# steering_wheel_V2.net
KiCad netlist of a schematic drawn in EAGLE
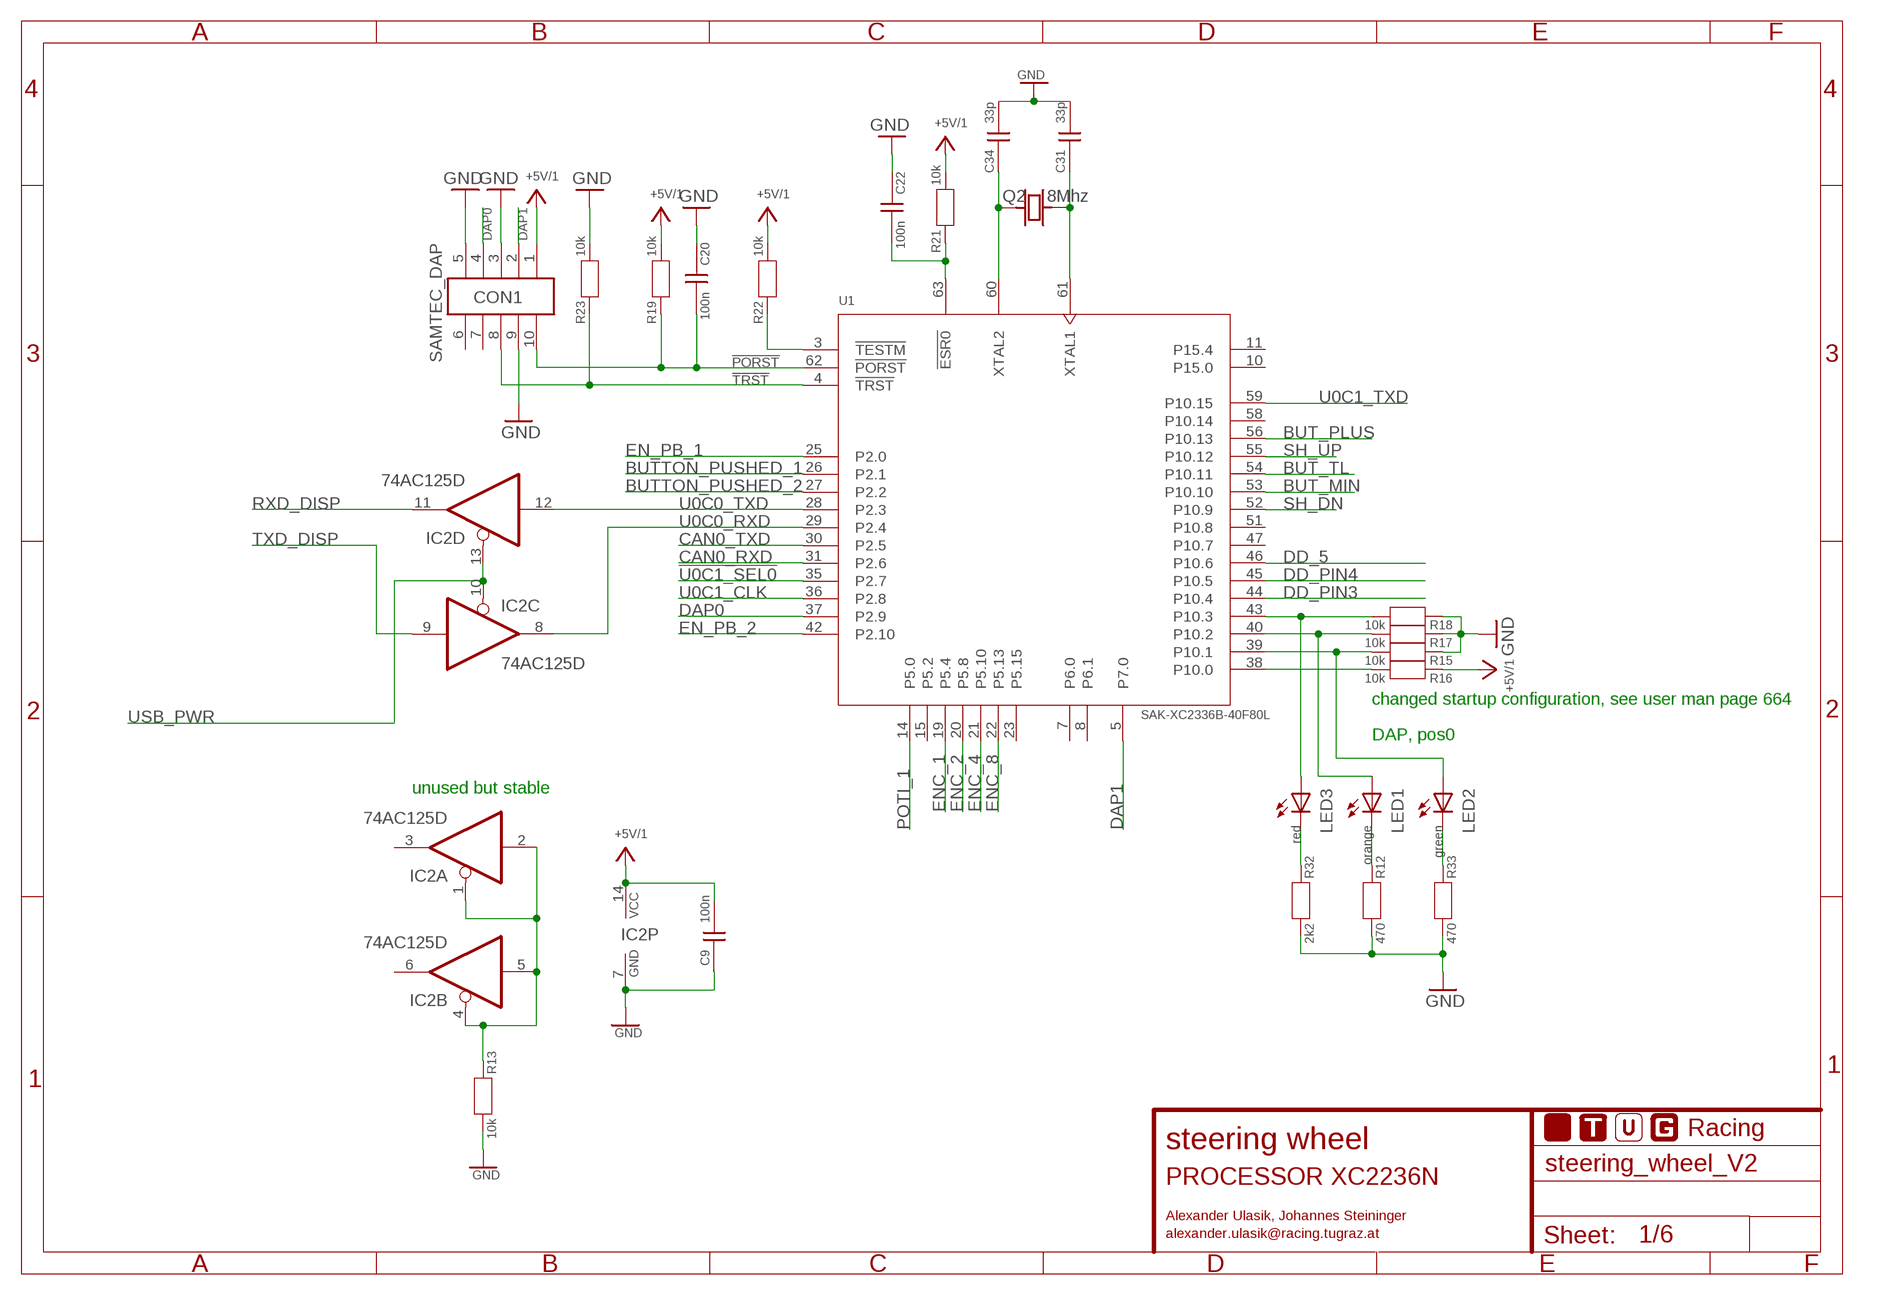
[diagram p0: schematic, sheet 1]
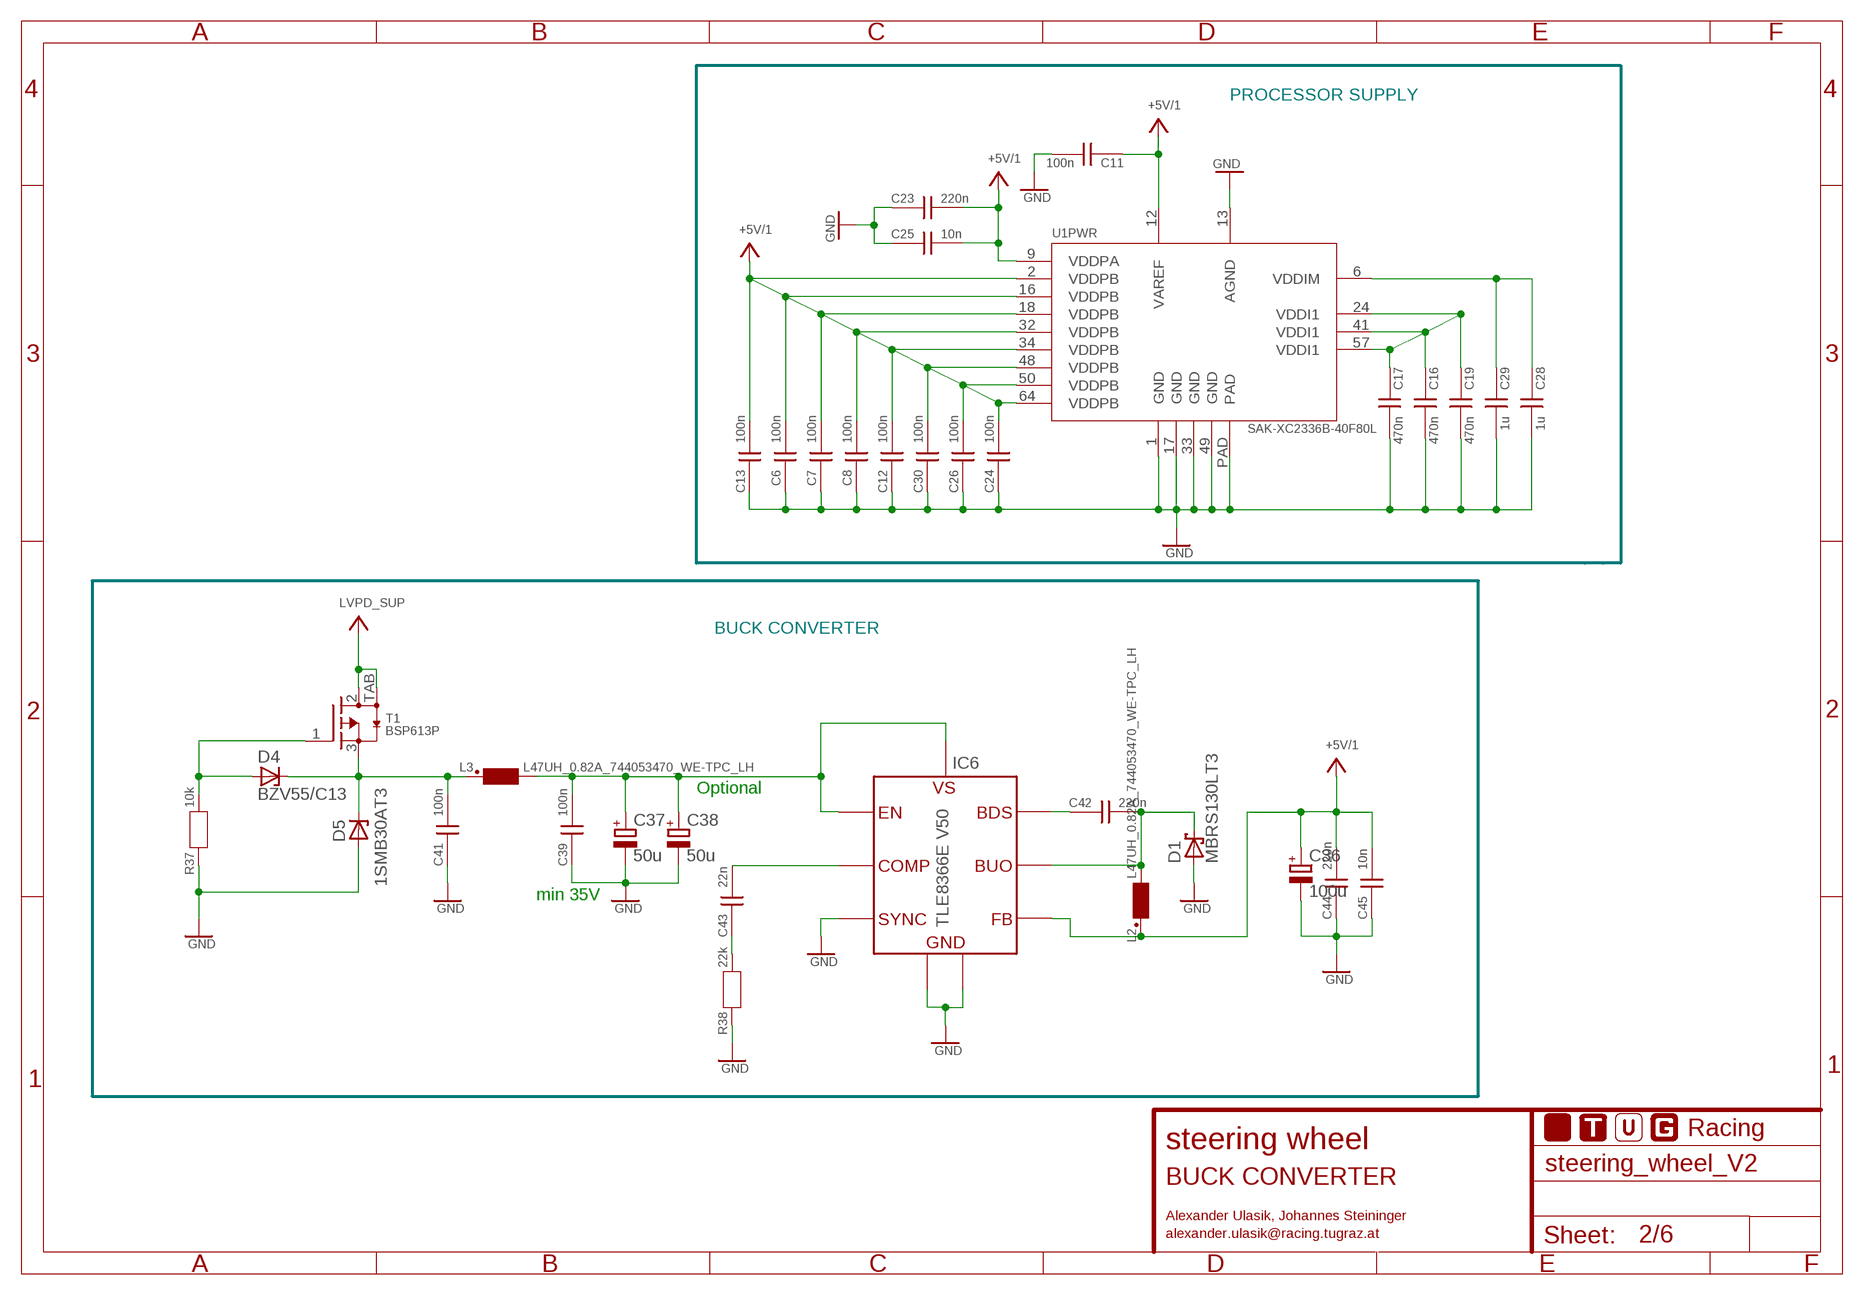
[diagram p1: schematic, sheet 2]
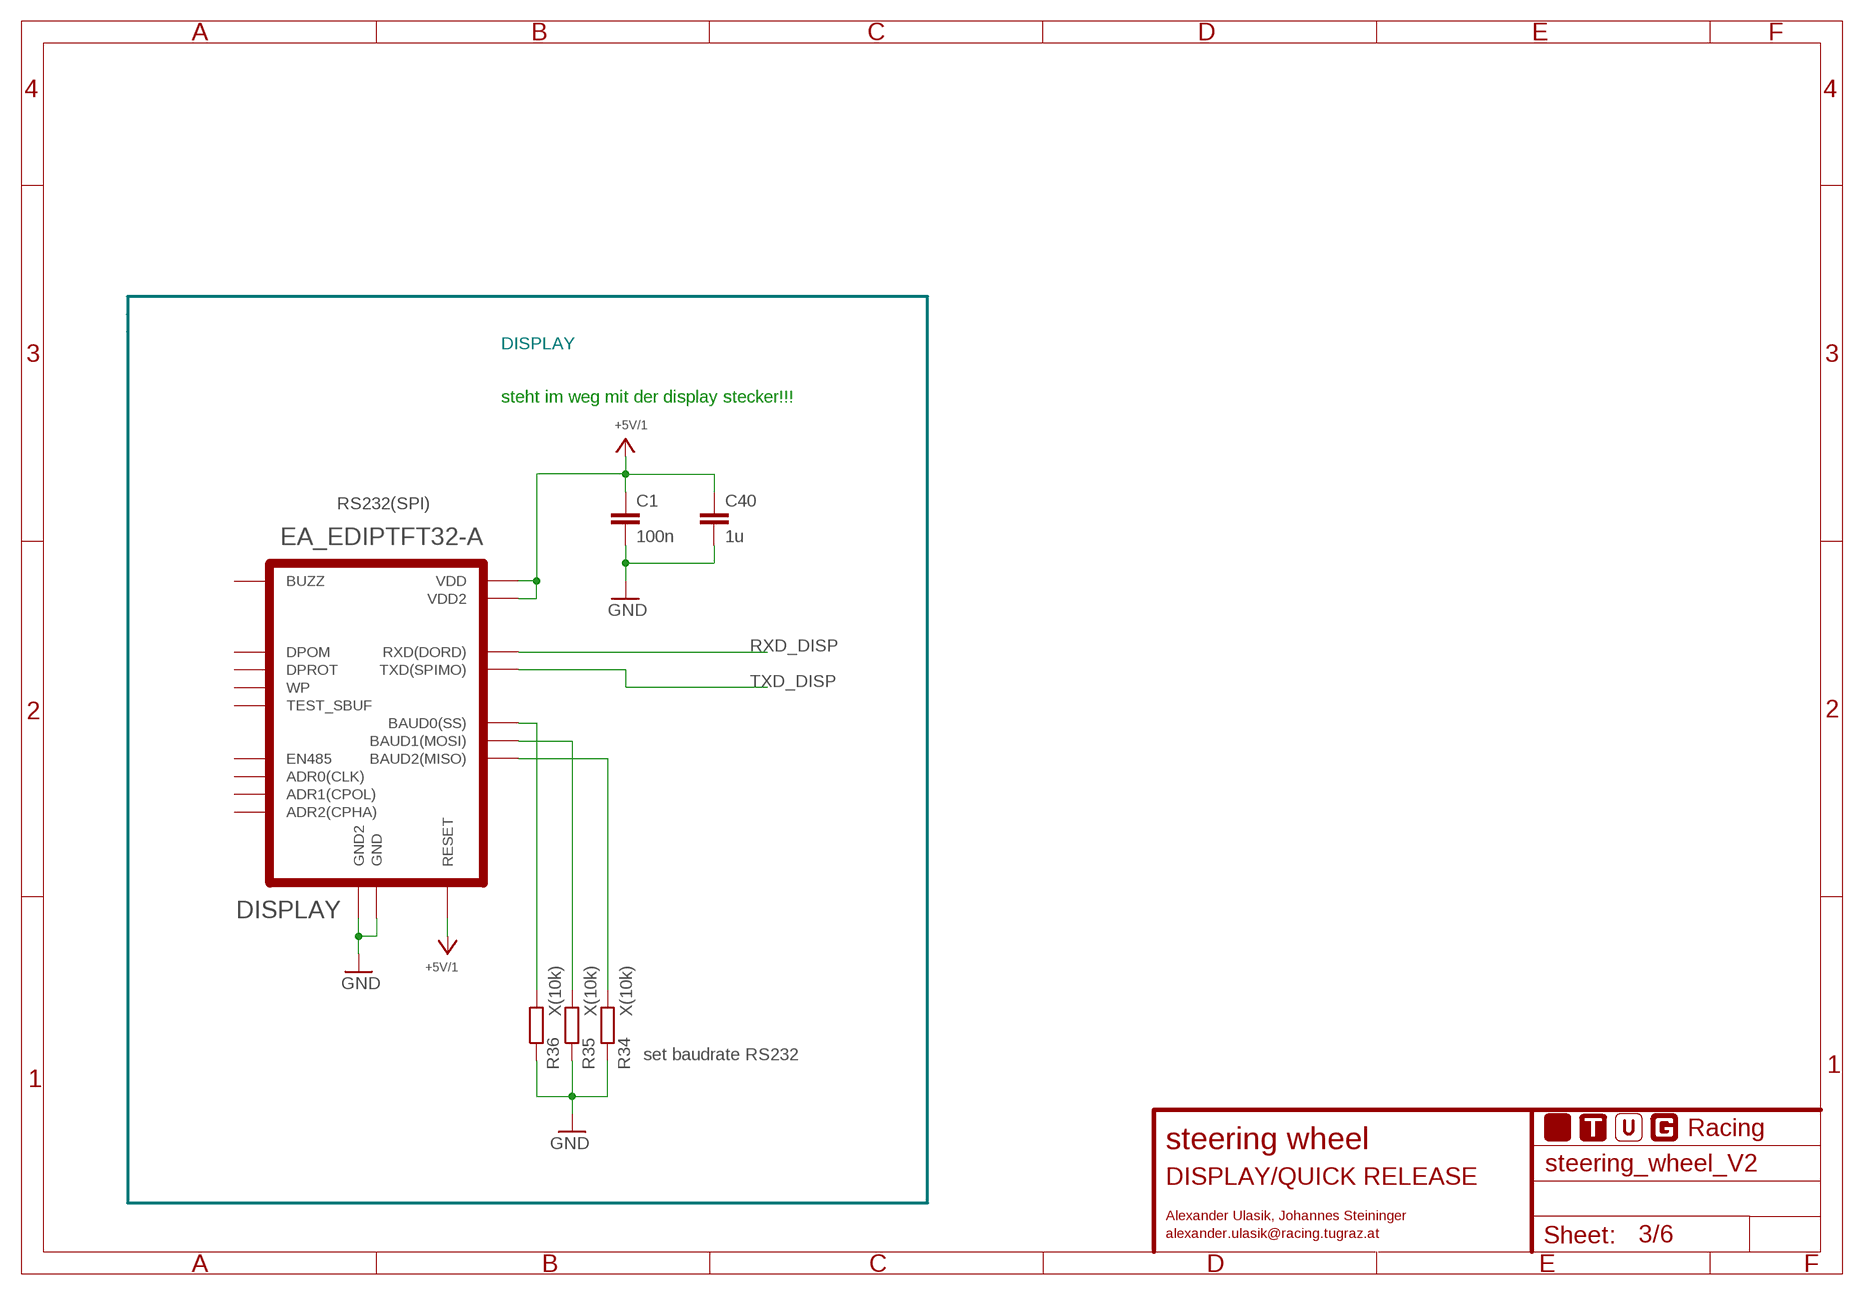
[diagram p2: schematic, sheet 3]
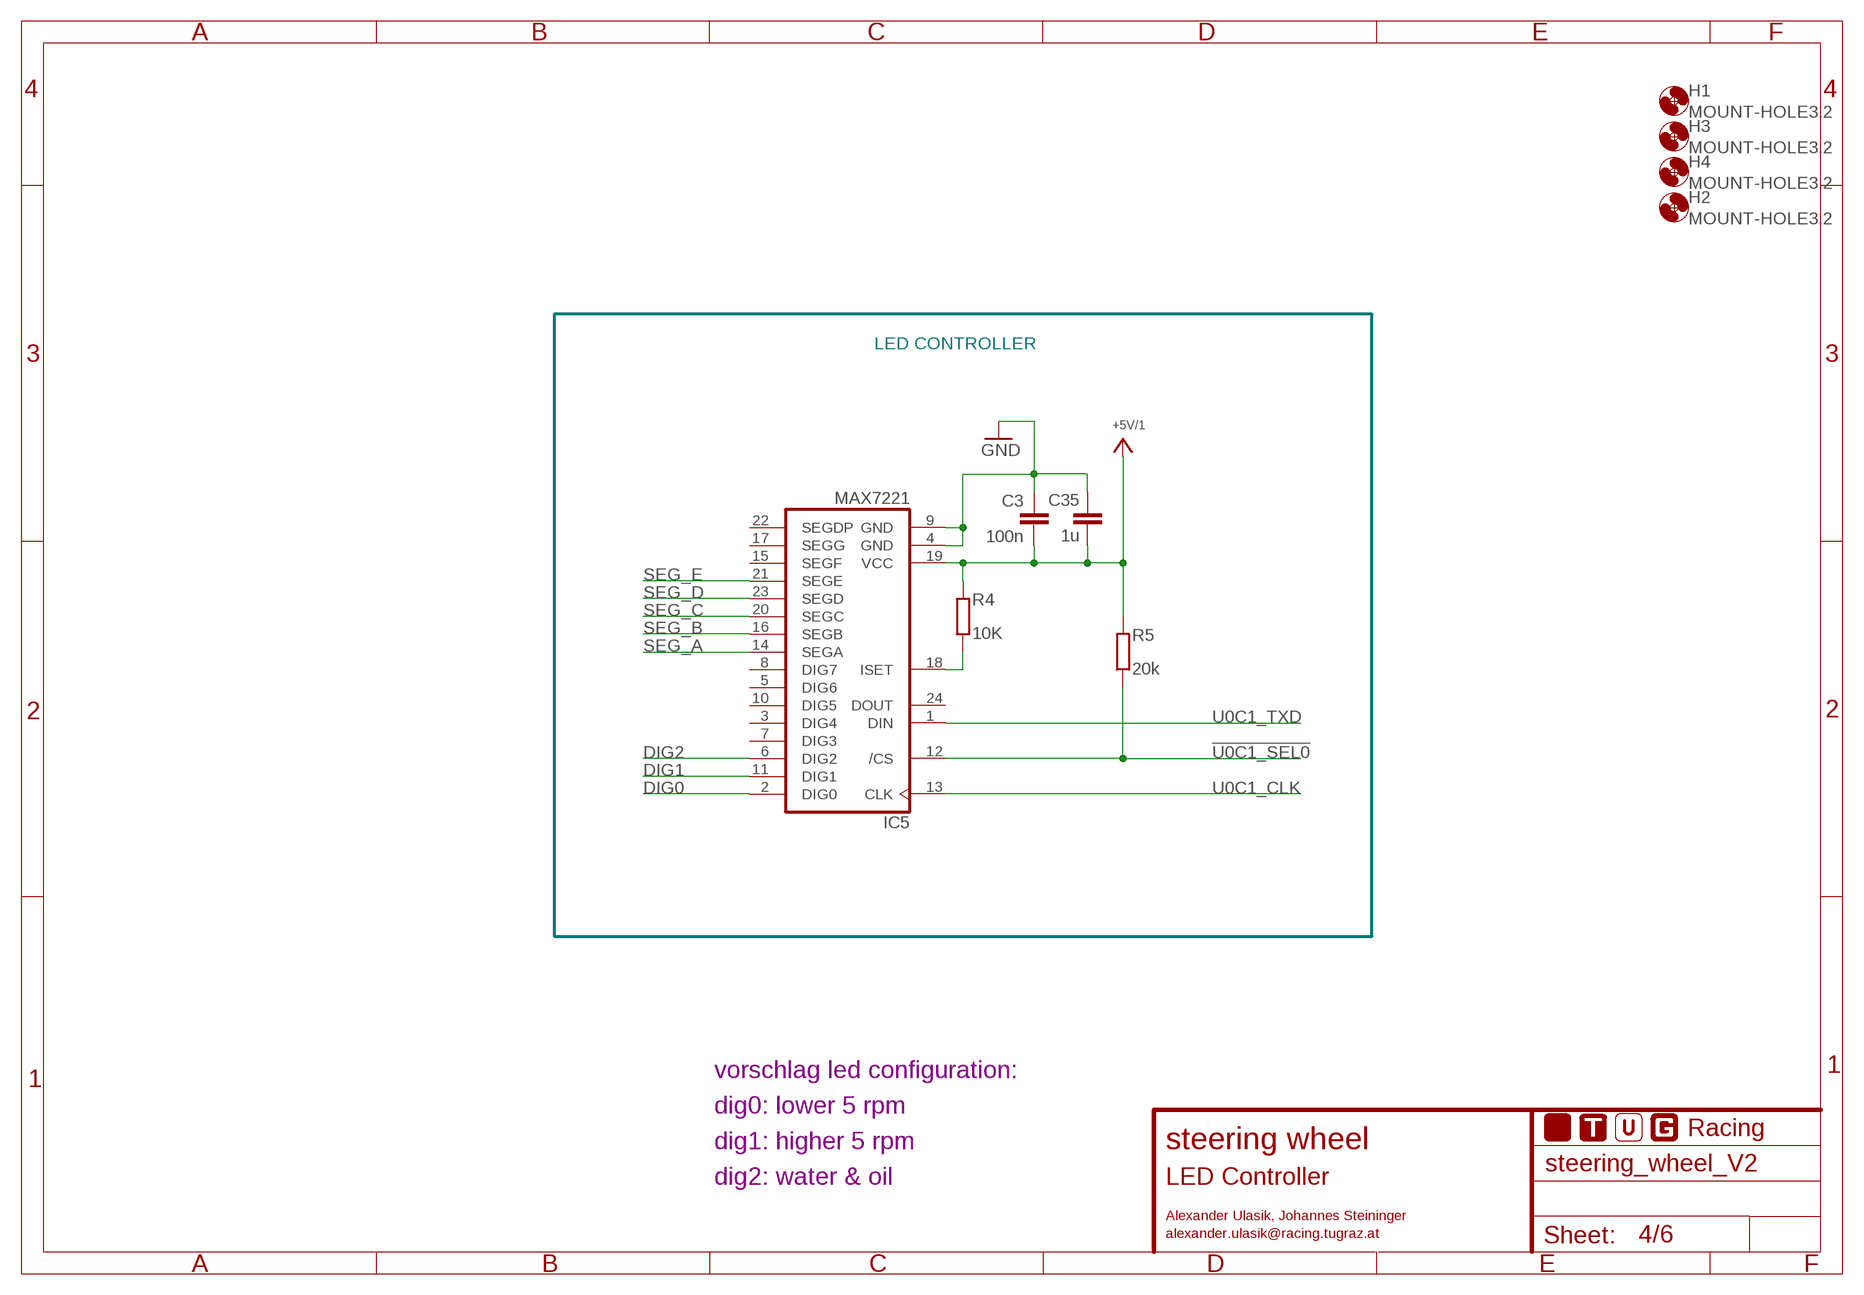
[diagram p3: schematic, sheet 4]
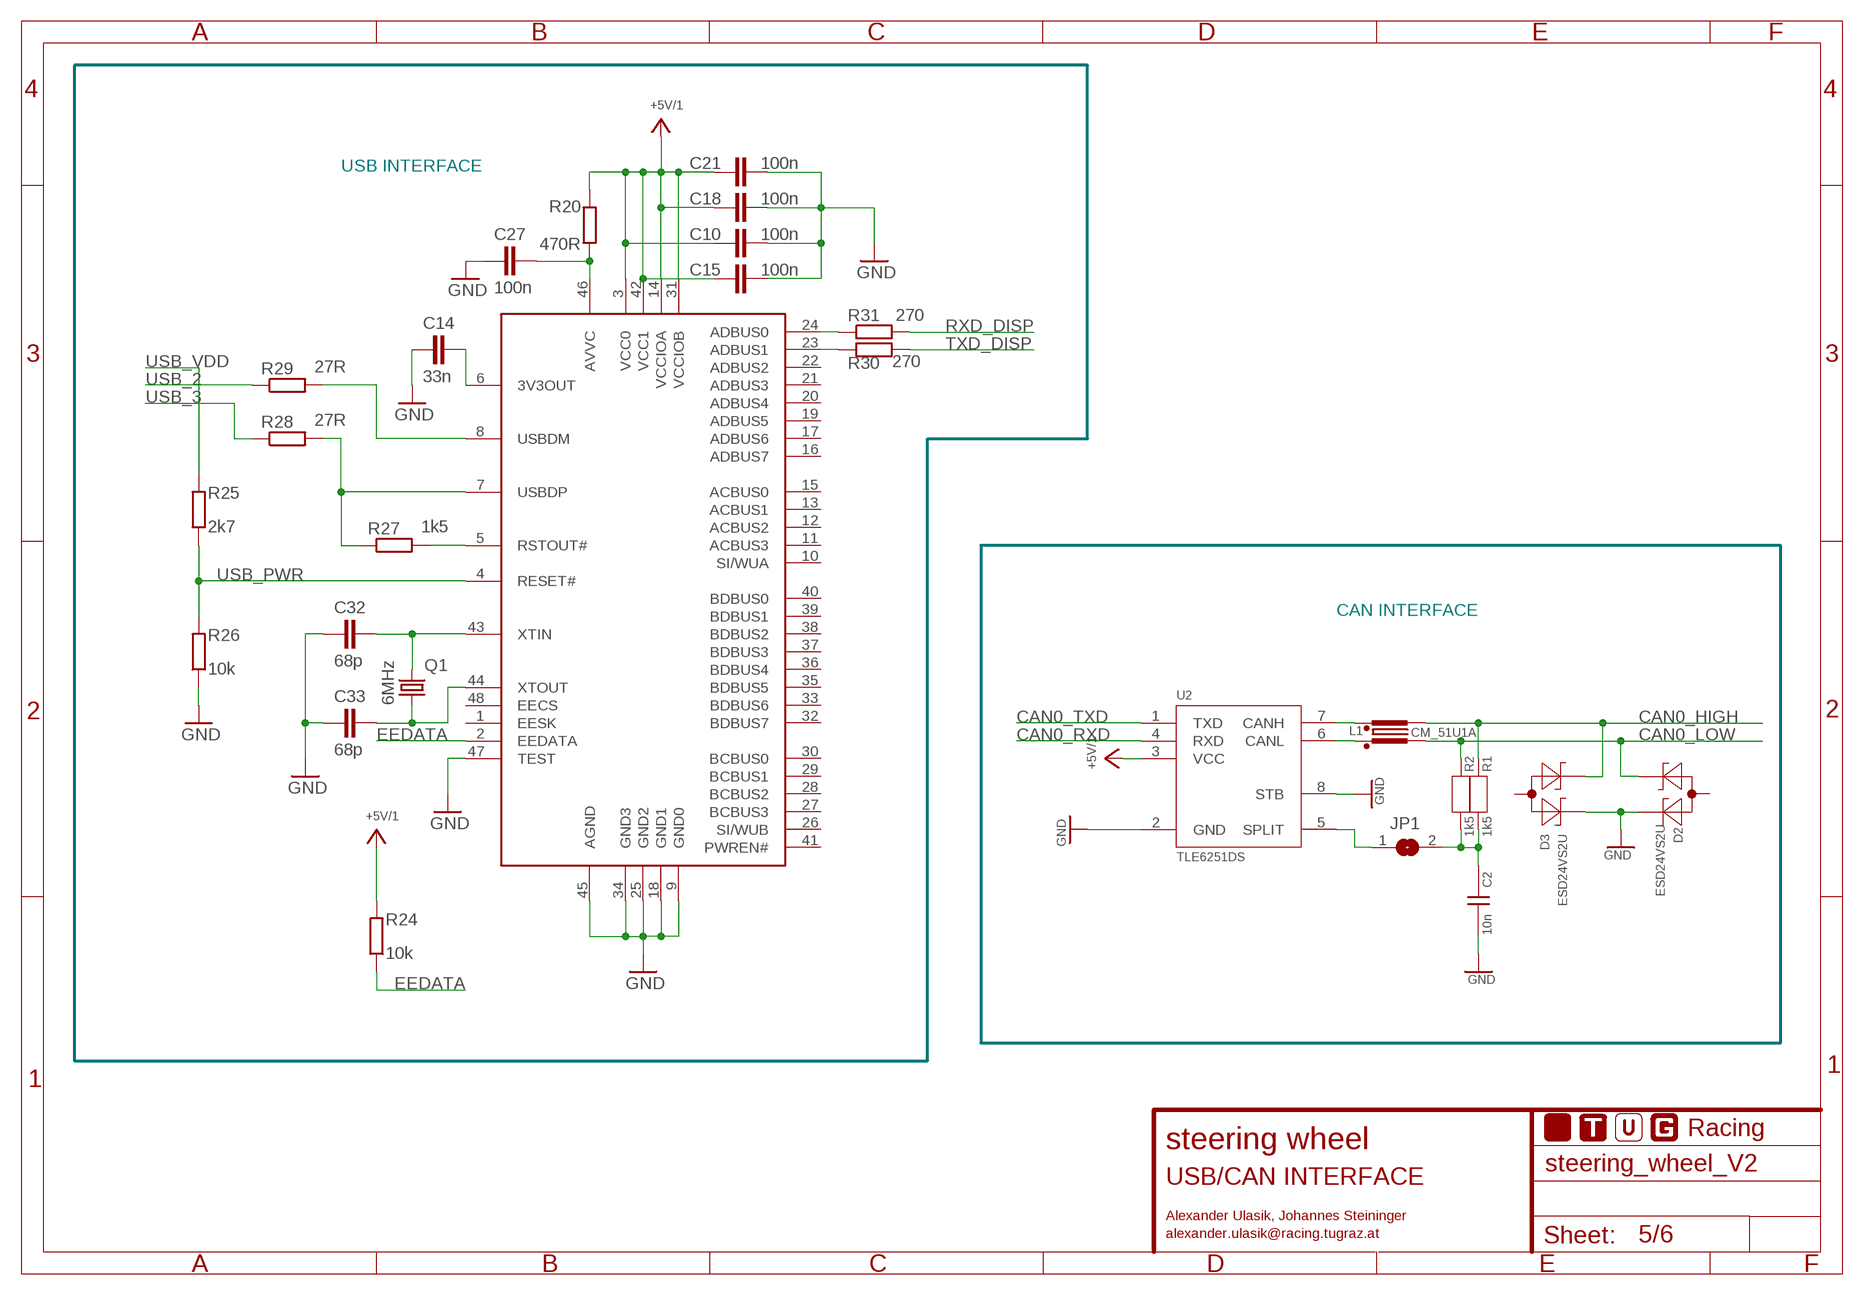
[diagram p4: schematic, sheet 5]
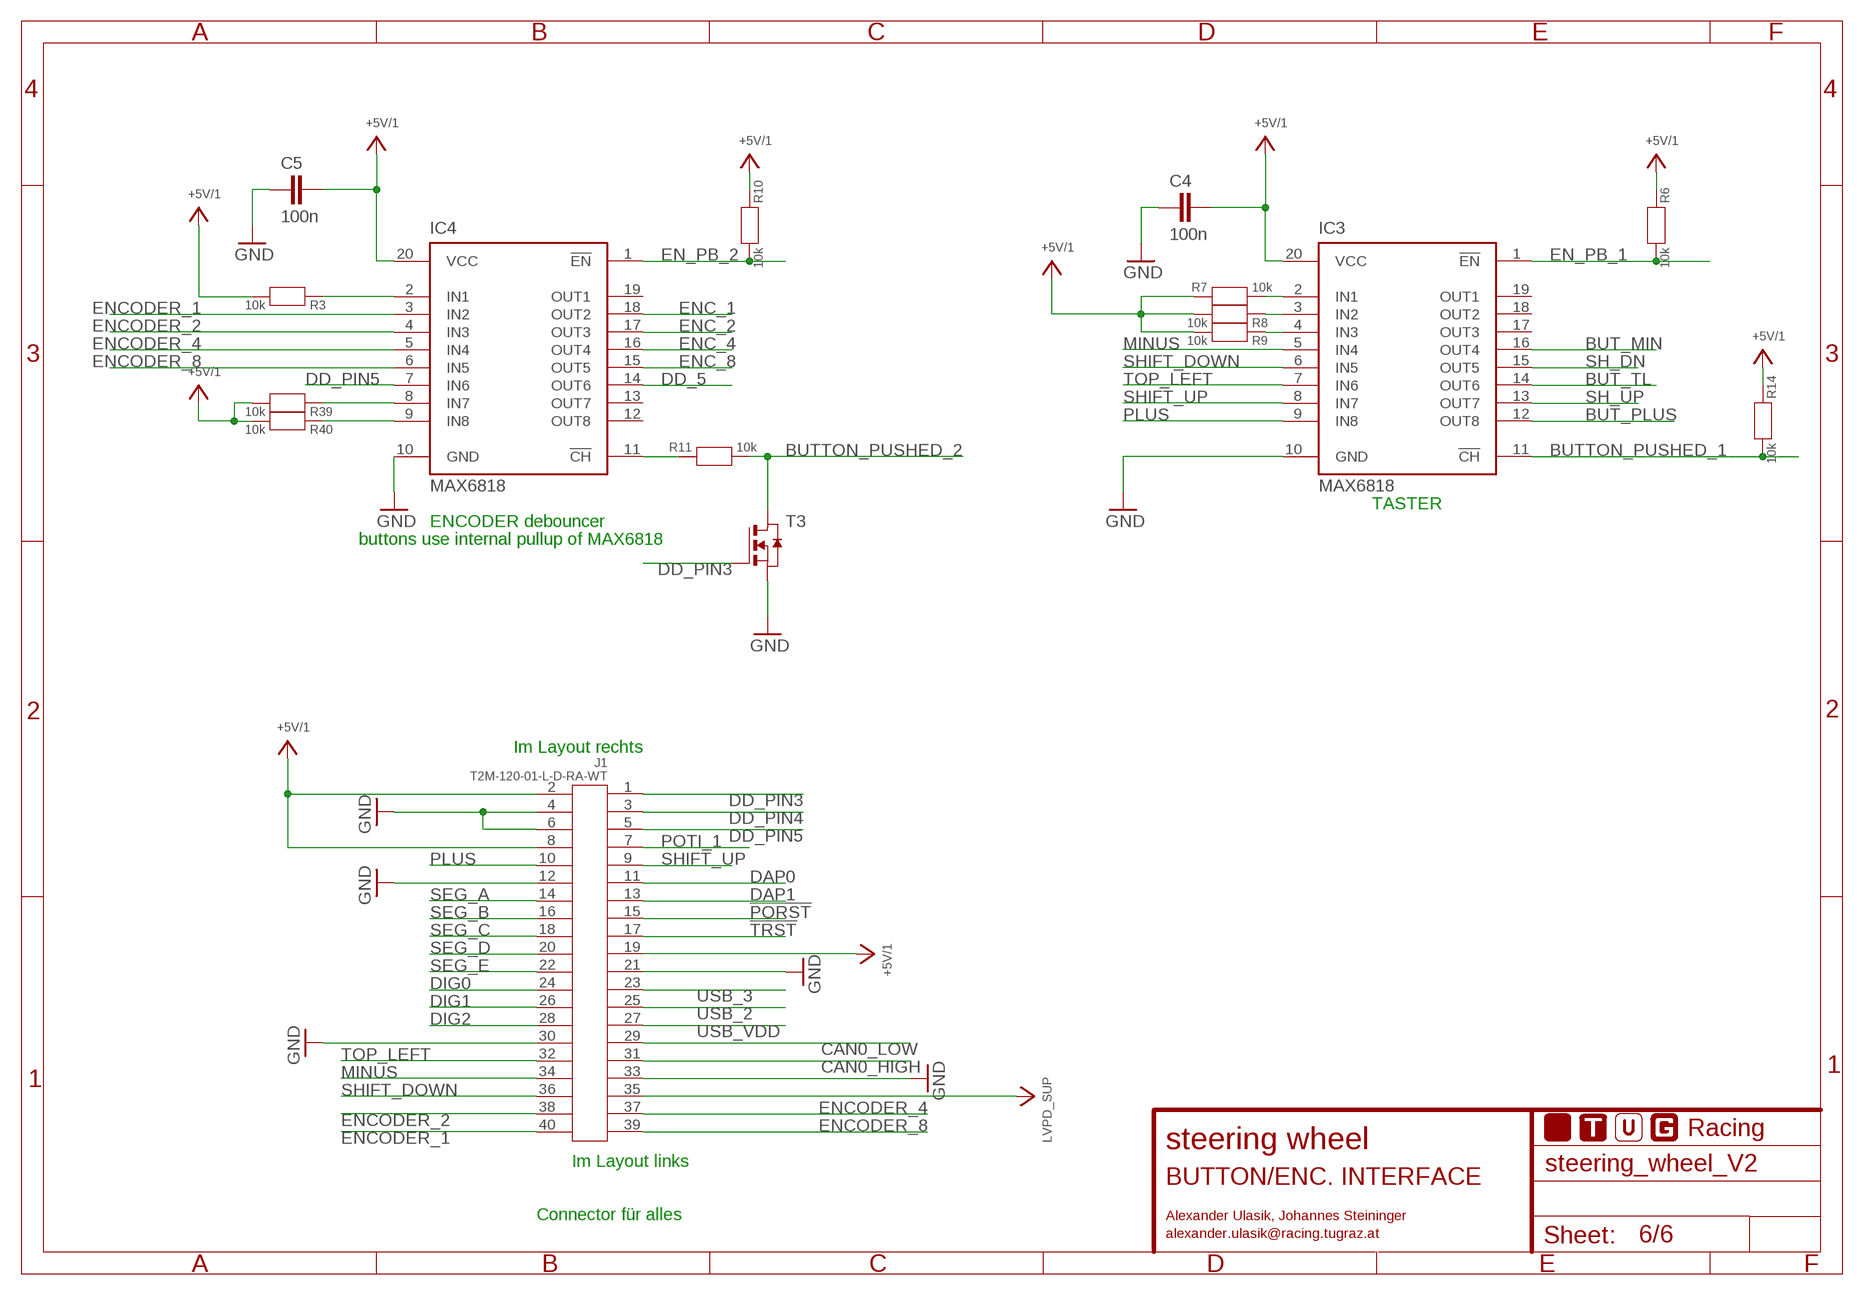
[diagram p5: schematic, sheet 6]

(export (version "E")
  (design (tool "Eeschema 10.0.6"))
  (components
    (comp (ref "C6")
      (value "100n")
      (footprint "eagle-import:2012M_0805")
      (libsource (lib "eagle-import") (part "C_2012M"))
    )
    (comp (ref "C7")
      (value "100n")
      (footprint "eagle-import:2012M_0805")
      (libsource (lib "eagle-import") (part "C_2012M"))
    )
    (comp (ref "C8")
      (value "100n")
      (footprint "eagle-import:2012M_0805")
      (libsource (lib "eagle-import") (part "C_2012M"))
    )
    (comp (ref "C11")
      (value "100n")
      (footprint "eagle-import:2012M_0805")
      (libsource (lib "eagle-import") (part "C_2012M"))
    )
    (comp (ref "C12")
      (value "100n")
      (footprint "eagle-import:2012M_0805")
      (libsource (lib "eagle-import") (part "C_2012M"))
    )
    (comp (ref "C13")
      (value "100n")
      (footprint "eagle-import:2012M_0805")
      (libsource (lib "eagle-import") (part "C_2012M"))
    )
    (comp (ref "C16")
      (value "470n")
      (footprint "eagle-import:2012M_0805")
      (libsource (lib "eagle-import") (part "C_2012M"))
    )
    (comp (ref "C17")
      (value "470n")
      (footprint "eagle-import:2012M_0805")
      (libsource (lib "eagle-import") (part "C_2012M"))
    )
    (comp (ref "C19")
      (value "470n")
      (footprint "eagle-import:2012M_0805")
      (libsource (lib "eagle-import") (part "C_2012M"))
    )
    (comp (ref "C23")
      (value "220n")
      (footprint "eagle-import:2012M_0805")
      (libsource (lib "eagle-import") (part "C_2012M"))
    )
    (comp (ref "C24")
      (value "100n")
      (footprint "eagle-import:2012M_0805")
      (libsource (lib "eagle-import") (part "C_2012M"))
    )
    (comp (ref "C25")
      (value "10n")
      (footprint "eagle-import:2012M_0805")
      (libsource (lib "eagle-import") (part "C_2012M"))
    )
    (comp (ref "C26")
      (value "100n")
      (footprint "eagle-import:2012M_0805")
      (libsource (lib "eagle-import") (part "C_2012M"))
    )
    (comp (ref "C28")
      (value "1u")
      (footprint "eagle-import:2012M_0805")
      (libsource (lib "eagle-import") (part "C_2012M"))
    )
    (comp (ref "C29")
      (value "1u")
      (footprint "eagle-import:2012M_0805")
      (libsource (lib "eagle-import") (part "C_2012M"))
    )
    (comp (ref "C30")
      (value "100n")
      (footprint "eagle-import:2012M_0805")
      (libsource (lib "eagle-import") (part "C_2012M"))
    )
    (comp (ref "C36")
      (value "100u")
      (footprint "eagle-import:E5-10,5")
      (libsource (lib "eagle-import") (part "CPOL-EUE5-10.5"))
    )
    (comp (ref "C37")
      (value "50u")
      (footprint "eagle-import:E5-10,5")
      (libsource (lib "eagle-import") (part "CPOL-EUE5-10.5"))
    )
    (comp (ref "C38")
      (value "50u")
      (footprint "eagle-import:E5-10,5")
      (libsource (lib "eagle-import") (part "CPOL-EUE5-10.5"))
    )
    (comp (ref "C39")
      (value "100n")
      (footprint "eagle-import:2012M_0805")
      (libsource (lib "eagle-import") (part "C_2012M"))
    )
    (comp (ref "C41")
      (value "100n")
      (footprint "eagle-import:2012M_0805")
      (libsource (lib "eagle-import") (part "C_2012M"))
    )
    (comp (ref "C42")
      (value "220n")
      (footprint "eagle-import:2012M_0805")
      (libsource (lib "eagle-import") (part "C_2012M"))
    )
    (comp (ref "C43")
      (value "22n")
      (footprint "eagle-import:2012M_0805")
      (libsource (lib "eagle-import") (part "C_2012M"))
    )
    (comp (ref "C44")
      (value "220n")
      (footprint "eagle-import:2012M_0805")
      (libsource (lib "eagle-import") (part "C_2012M"))
    )
    (comp (ref "C45")
      (value "10n")
      (footprint "eagle-import:2012M_0805")
      (libsource (lib "eagle-import") (part "C_2012M"))
    )
    (comp (ref "D1")
      (value "MBRS130LT3")
      (footprint "eagle-import:SMB")
      (libsource (lib "eagle-import") (part "MBRS130LT3"))
    )
    (comp (ref "D4")
      (value "BZV55/C13")
      (footprint "eagle-import:SOD80C")
      (libsource (lib "eagle-import") (part "diode_ZENER-DIODESOD80C"))
    )
    (comp (ref "D5")
      (value "1SMB30AT3")
      (footprint "eagle-import:SMB")
      (libsource (lib "eagle-import") (part "ZENER-DIODESMB"))
    )
    (comp (ref "FRAME4")
      (value "A4L-LOC-RACING-BRD-TPLACE")
      (footprint "eagle-import:LOGO_RACING_BRD_TPLACE")
      (fields
        (field (name "FRAME_EMAIL") "alexander.ulasik@racing.tugraz.at")
        (field (name "FRAME_SUBTITLE") "BUCK CONVERTER")
        (field (name "FRAME_TITLE") "steering wheel")
        (field (name "FRAME_USER") "Alexander Ulasik, Johannes Steininger")
      )
      (libsource (lib "eagle-import") (part "A4L-LOC-RACING-BRD-TPLACE"))
    )
    (comp (ref "IC6")
      (value "TLE8366E V50")
      (footprint "eagle-import:SOIC08-II")
      (libsource (lib "eagle-import") (part "TLE8366-II"))
    )
    (comp (ref "L2")
      (value "L47UH_0.82A_744053470_WE-TPC_LH")
      (footprint "eagle-import:WE-TPC_LH")
      (libsource (lib "eagle-import") (part "L_WE-TPC_LH47UH_0.82A_744053470"))
    )
    (comp (ref "L3")
      (value "L47UH_0.82A_744053470_WE-TPC_LH")
      (footprint "eagle-import:WE-TPC_LH")
      (libsource (lib "eagle-import") (part "L_WE-TPC_LH47UH_0.82A_744053470"))
    )
    (comp (ref "R37")
      (value "10k")
      (footprint "eagle-import:2012M_0805")
      (libsource (lib "eagle-import") (part "R_2012M"))
    )
    (comp (ref "R38")
      (value "22k")
      (footprint "eagle-import:2012M_0805")
      (libsource (lib "eagle-import") (part "R_2012M"))
    )
    (comp (ref "T1")
      (value "BSP613P")
      (footprint "eagle-import:SOT223-3")
      (libsource (lib "eagle-import") (part "BSP613P"))
    )
    (comp (ref "U1")
      (value "SAK-XC2336B-40F80L")
      (footprint "eagle-import:PG-LQFP-64-6")
      (libsource (lib "eagle-import") (part "SAK-XC2336B-40F80L"))
    )
    (comp (ref "C9")
      (value "100n")
      (footprint "eagle-import:1608M_0603")
      (libsource (lib "eagle-import") (part "C_1608M"))
    )
    (comp (ref "C20")
      (value "100n")
      (footprint "eagle-import:2012M_0805")
      (libsource (lib "eagle-import") (part "C_2012M"))
    )
    (comp (ref "C22")
      (value "100n")
      (footprint "eagle-import:2012M_0805")
      (libsource (lib "eagle-import") (part "C_2012M"))
    )
    (comp (ref "C31")
      (value "33p")
      (footprint "eagle-import:1608M_0603")
      (libsource (lib "eagle-import") (part "C_1608M"))
    )
    (comp (ref "C34")
      (value "33p")
      (footprint "eagle-import:1608M_0603")
      (libsource (lib "eagle-import") (part "C_1608M"))
    )
    (comp (ref "CON1")
      (value "SAMTEC_DAP")
      (footprint "eagle-import:FTSH-105-01-XXX-DV-K")
      (libsource (lib "eagle-import") (part "SAMTEC_DAP"))
    )
    (comp (ref "FRAME1")
      (value "A4L-LOC-RACING-NOLOGO")
      (footprint "eagle-import:NOLOGO")
      (fields
        (field (name "FRAME_EMAIL") "alexander.ulasik@racing.tugraz.at")
        (field (name "FRAME_SUBTITLE") "PROCESSOR XC2236N ")
        (field (name "FRAME_TITLE") "steering wheel")
        (field (name "FRAME_USER") "Alexander Ulasik, Johannes Steininger")
      )
      (libsource (lib "eagle-import") (part "A4L-LOC-RACING-NOLOGO"))
    )
    (comp (ref "IC2")
      (value "74AC125D")
      (footprint "eagle-import:SO14")
      (libsource (lib "eagle-import") (part "74125DAC"))
    )
    (comp (ref "LED1")
      (value "LEDCHIPLED_0805")
      (footprint "eagle-import:CHIPLED_0805")
      (fields (field (name "ASMT-RJ45-AQ502") "orange"))
      (libsource (lib "eagle-import") (part "LEDCHIPLED_0805"))
    )
    (comp (ref "LED2")
      (value "LEDCHIPLED_0805")
      (footprint "eagle-import:CHIPLED_0805")
      (fields (field (name "ASMT-RF45-AQ502") "green"))
      (libsource (lib "eagle-import") (part "LEDCHIPLED_0805"))
    )
    (comp (ref "LED3")
      (value "LEDCHIPLED_0805")
      (footprint "eagle-import:CHIPLED_0805")
      (fields (field (name "ASMT-RR45-AQ502") "red"))
      (libsource (lib "eagle-import") (part "LEDCHIPLED_0805"))
    )
    (comp (ref "Q2")
      (value "8Mhz")
      (footprint "eagle-import:ABMM2")
      (libsource (lib "eagle-import") (part "ABMM2"))
    )
    (comp (ref "R12")
      (value "470")
      (footprint "eagle-import:2012M_0805")
      (libsource (lib "eagle-import") (part "R_2012M"))
    )
    (comp (ref "R13")
      (value "10k")
      (footprint "eagle-import:2012M_0805")
      (libsource (lib "eagle-import") (part "R_2012M"))
    )
    (comp (ref "R15")
      (value "10k")
      (footprint "eagle-import:2012M_0805")
      (libsource (lib "eagle-import") (part "R_2012M"))
    )
    (comp (ref "R16")
      (value "10k")
      (footprint "eagle-import:2012M_0805")
      (libsource (lib "eagle-import") (part "R_2012M"))
    )
    (comp (ref "R17")
      (value "10k")
      (footprint "eagle-import:2012M_0805")
      (libsource (lib "eagle-import") (part "R_2012M"))
    )
    (comp (ref "R18")
      (value "10k")
      (footprint "eagle-import:2012M_0805")
      (libsource (lib "eagle-import") (part "R_2012M"))
    )
    (comp (ref "R19")
      (value "10k")
      (footprint "eagle-import:2012M_0805")
      (libsource (lib "eagle-import") (part "R_2012M"))
    )
    (comp (ref "R21")
      (value "10k")
      (footprint "eagle-import:2012M_0805")
      (libsource (lib "eagle-import") (part "R_2012M"))
    )
    (comp (ref "R22")
      (value "10k")
      (footprint "eagle-import:2012M_0805")
      (libsource (lib "eagle-import") (part "R_2012M"))
    )
    (comp (ref "R23")
      (value "10k")
      (footprint "eagle-import:2012M_0805")
      (libsource (lib "eagle-import") (part "R_2012M"))
    )
    (comp (ref "R32")
      (value "2k2")
      (footprint "eagle-import:2012M_0805")
      (libsource (lib "eagle-import") (part "R_2012M"))
    )
    (comp (ref "R33")
      (value "470")
      (footprint "eagle-import:2012M_0805")
      (libsource (lib "eagle-import") (part "R_2012M"))
    )
    (comp (ref "C3")
      (value "100n")
      (footprint "eagle-import:C0805")
      (libsource (lib "eagle-import") (part "C-EUC0805"))
    )
    (comp (ref "C35")
      (value "1u")
      (footprint "eagle-import:C0805")
      (libsource (lib "eagle-import") (part "C-EUC0805"))
    )
    (comp (ref "FRAME5")
      (value "A4L-LOC-RACING-NOLOGO")
      (footprint "eagle-import:NOLOGO")
      (fields
        (field (name "FRAME_EMAIL") "alexander.ulasik@racing.tugraz.at")
        (field (name "FRAME_SUBTITLE") "LED Controller")
        (field (name "FRAME_TITLE") "steering wheel")
        (field (name "FRAME_USER") "Alexander Ulasik, Johannes Steininger")
      )
      (libsource (lib "eagle-import") (part "A4L-LOC-RACING-NOLOGO"))
    )
    (comp (ref "H1")
      (value "MOUNT-HOLE3.2")
      (footprint "eagle-import:3,2")
      (libsource (lib "eagle-import") (part "MOUNT-HOLE3.2"))
    )
    (comp (ref "H2")
      (value "MOUNT-HOLE3.2")
      (footprint "eagle-import:3,2")
      (libsource (lib "eagle-import") (part "MOUNT-HOLE3.2"))
    )
    (comp (ref "H3")
      (value "MOUNT-HOLE3.2")
      (footprint "eagle-import:3,2")
      (libsource (lib "eagle-import") (part "MOUNT-HOLE3.2"))
    )
    (comp (ref "H4")
      (value "MOUNT-HOLE3.2")
      (footprint "eagle-import:3,2")
      (libsource (lib "eagle-import") (part "MOUNT-HOLE3.2"))
    )
    (comp (ref "IC5")
      (value "MAX7221")
      (footprint "eagle-import:SO_W24")
      (libsource (lib "eagle-import") (part "MAX7221"))
    )
    (comp (ref "R4")
      (value "10K")
      (footprint "eagle-import:M0805")
      (libsource (lib "eagle-import") (part "R-EU_M0805"))
    )
    (comp (ref "R5")
      (value "20k")
      (footprint "eagle-import:M0805")
      (libsource (lib "eagle-import") (part "R-EU_M0805"))
    )
    (comp (ref "C4")
      (value "100n")
      (footprint "eagle-import:C0805")
      (libsource (lib "eagle-import") (part "C-EUC0805"))
    )
    (comp (ref "C5")
      (value "100n")
      (footprint "eagle-import:C0805")
      (libsource (lib "eagle-import") (part "C-EUC0805"))
    )
    (comp (ref "FRAME2")
      (value "A4L-LOC-RACING-NOLOGO")
      (footprint "eagle-import:NOLOGO")
      (fields
        (field (name "FRAME_EMAIL") "alexander.ulasik@racing.tugraz.at")
        (field (name "FRAME_SUBTITLE") "BUTTON/ENC. INTERFACE")
        (field (name "FRAME_TITLE") "steering wheel")
        (field (name "FRAME_USER") "Alexander Ulasik, Johannes Steininger")
      )
      (libsource (lib "eagle-import") (part "A4L-LOC-RACING-NOLOGO"))
    )
    (comp (ref "IC3")
      (value "MAX6818")
      (footprint "eagle-import:SSOP20")
      (libsource (lib "eagle-import") (part "MAX6818"))
    )
    (comp (ref "IC4")
      (value "MAX6818")
      (footprint "eagle-import:SSOP20")
      (libsource (lib "eagle-import") (part "MAX6818"))
    )
    (comp (ref "J1")
      (value "T2M-120-01-L-D-RA-WT")
      (footprint "eagle-import:T2M-120-01-L-D-RA-WT")
      (libsource (lib "eagle-import") (part "T2M-120-01-L-D-RA-WT"))
    )
    (comp (ref "R3")
      (value "10k")
      (footprint "eagle-import:2012M_0805")
      (libsource (lib "eagle-import") (part "R_2012M"))
    )
    (comp (ref "R6")
      (value "10k")
      (footprint "eagle-import:2012M_0805")
      (libsource (lib "eagle-import") (part "R_2012M"))
    )
    (comp (ref "R7")
      (value "10k")
      (footprint "eagle-import:2012M_0805")
      (libsource (lib "eagle-import") (part "R_2012M"))
    )
    (comp (ref "R8")
      (value "10k")
      (footprint "eagle-import:2012M_0805")
      (libsource (lib "eagle-import") (part "R_2012M"))
    )
    (comp (ref "R9")
      (value "10k")
      (footprint "eagle-import:2012M_0805")
      (libsource (lib "eagle-import") (part "R_2012M"))
    )
    (comp (ref "R10")
      (value "10k")
      (footprint "eagle-import:2012M_0805")
      (libsource (lib "eagle-import") (part "R_2012M"))
    )
    (comp (ref "R11")
      (value "10k")
      (footprint "eagle-import:2012M_0805")
      (libsource (lib "eagle-import") (part "R_2012M"))
    )
    (comp (ref "R14")
      (value "10k")
      (footprint "eagle-import:2012M_0805")
      (libsource (lib "eagle-import") (part "R_2012M"))
    )
    (comp (ref "R39")
      (value "10k")
      (footprint "eagle-import:2012M_0805")
      (libsource (lib "eagle-import") (part "R_2012M"))
    )
    (comp (ref "R40")
      (value "10k")
      (footprint "eagle-import:2012M_0805")
      (libsource (lib "eagle-import") (part "R_2012M"))
    )
    (comp (ref "T3")
      (value "NMOSSOT23")
      (footprint "eagle-import:SOT-23")
      (libsource (lib "eagle-import") (part "NMOSSOT23"))
    )
    (comp (ref "C2")
      (value "10n")
      (footprint "eagle-import:2012M_0805")
      (libsource (lib "eagle-import") (part "C_2012M"))
    )
    (comp (ref "C10")
      (value "100n")
      (footprint "eagle-import:C0805")
      (libsource (lib "eagle-import") (part "C-EUC0805"))
    )
    (comp (ref "C14")
      (value "33n")
      (footprint "eagle-import:C0805")
      (libsource (lib "eagle-import") (part "C-EUC0805"))
    )
    (comp (ref "C15")
      (value "100n")
      (footprint "eagle-import:C0805")
      (libsource (lib "eagle-import") (part "C-EUC0805"))
    )
    (comp (ref "C18")
      (value "100n")
      (footprint "eagle-import:C0805")
      (libsource (lib "eagle-import") (part "C-EUC0805"))
    )
    (comp (ref "C21")
      (value "100n")
      (footprint "eagle-import:C0805")
      (libsource (lib "eagle-import") (part "C-EUC0805"))
    )
    (comp (ref "C27")
      (value "100n")
      (footprint "eagle-import:C0805")
      (libsource (lib "eagle-import") (part "C-EUC0805"))
    )
    (comp (ref "C32")
      (value "68p")
      (footprint "eagle-import:C0805")
      (libsource (lib "eagle-import") (part "C-EUC0805"))
    )
    (comp (ref "C33")
      (value "68p")
      (footprint "eagle-import:C0805")
      (libsource (lib "eagle-import") (part "C-EUC0805"))
    )
    (comp (ref "D2")
      (value "ESD24VS2U")
      (footprint "eagle-import:SOT23-3")
      (libsource (lib "eagle-import") (part "ESD24VS2U"))
    )
    (comp (ref "D3")
      (value "ESD24VS2U")
      (footprint "eagle-import:SOT23-3")
      (libsource (lib "eagle-import") (part "ESD24VS2U"))
    )
    (comp (ref "FRAME6")
      (value "A4L-LOC-RACING-BRD-TPLACE")
      (footprint "eagle-import:LOGO_RACING_BRD_TPLACE")
      (fields
        (field (name "FRAME_EMAIL") "alexander.ulasik@racing.tugraz.at")
        (field (name "FRAME_SUBTITLE") "USB/CAN INTERFACE")
        (field (name "FRAME_TITLE") "steering wheel")
        (field (name "FRAME_USER") "Alexander Ulasik, Johannes Steininger")
      )
      (libsource (lib "eagle-import") (part "A4L-LOC-RACING-BRD-TPLACE"))
    )
    (comp (ref "IC1")
      (value "FT2232")
      (footprint "eagle-import:LQFP48")
      (libsource (lib "eagle-import") (part "FT2232L"))
    )
    (comp (ref "JP1") (value "SJ") (footprint "eagle-import:SJ") (libsource (lib "eagle-import") (part "SJ")))
    (comp (ref "L1")
      (value "CM_51U1A")
      (footprint "eagle-import:WE-SL2")
      (libsource (lib "eagle-import") (part "CM_51U1A"))
    )
    (comp (ref "Q1")
      (value "6MHz")
      (footprint "eagle-import:HC49U70")
      (libsource (lib "eagle-import") (part "CRYSTALHC49U70"))
    )
    (comp (ref "R1")
      (value "1k5")
      (footprint "eagle-import:2012M_0805")
      (libsource (lib "eagle-import") (part "R_2012M"))
    )
    (comp (ref "R2")
      (value "1k5")
      (footprint "eagle-import:2012M_0805")
      (libsource (lib "eagle-import") (part "R_2012M"))
    )
    (comp (ref "R20")
      (value "470R")
      (footprint "eagle-import:R0805")
      (libsource (lib "eagle-import") (part "R-EU_R0805"))
    )
    (comp (ref "R24")
      (value "10k")
      (footprint "eagle-import:R0805")
      (libsource (lib "eagle-import") (part "R-EU_R0805"))
    )
    (comp (ref "R25")
      (value "2k7")
      (footprint "eagle-import:R0805")
      (libsource (lib "eagle-import") (part "R-EU_R0805"))
    )
    (comp (ref "R26")
      (value "10k")
      (footprint "eagle-import:R0805")
      (libsource (lib "eagle-import") (part "R-EU_R0805"))
    )
    (comp (ref "R27")
      (value "1k5")
      (footprint "eagle-import:R0805")
      (libsource (lib "eagle-import") (part "R-EU_R0805"))
    )
    (comp (ref "R28")
      (value "27R")
      (footprint "eagle-import:R0805")
      (libsource (lib "eagle-import") (part "R-EU_R0805"))
    )
    (comp (ref "R29")
      (value "27R")
      (footprint "eagle-import:R0805")
      (libsource (lib "eagle-import") (part "R-EU_R0805"))
    )
    (comp (ref "R30")
      (value "270")
      (footprint "eagle-import:R0805")
      (libsource (lib "eagle-import") (part "R-EU_R0805"))
    )
    (comp (ref "R31")
      (value "270")
      (footprint "eagle-import:R0805")
      (libsource (lib "eagle-import") (part "R-EU_R0805"))
    )
    (comp (ref "U2")
      (value "TLE6251DS")
      (footprint "eagle-import:SO8")
      (libsource (lib "eagle-import") (part "TLE6251DS"))
    )
    (comp (ref "C1")
      (value "100n")
      (footprint "eagle-import:C0805")
      (libsource (lib "eagle-import") (part "C-EUC0805"))
    )
    (comp (ref "C40")
      (value "1u")
      (footprint "eagle-import:C0805")
      (libsource (lib "eagle-import") (part "C-EUC0805"))
    )
    (comp (ref "DISPLAY")
      (value "EA_EDIPTFT32-A")
      (footprint "eagle-import:EDIPTFT32-A")
      (libsource (lib "eagle-import") (part "EA_EDIPTFT32-A-SR232"))
    )
    (comp (ref "FRAME3")
      (value "A4L-LOC-RACING-NOLOGO")
      (footprint "eagle-import:NOLOGO")
      (fields
        (field (name "FRAME_EMAIL") "alexander.ulasik@racing.tugraz.at")
        (field (name "FRAME_SUBTITLE") "DISPLAY/QUICK RELEASE")
        (field (name "FRAME_TITLE") "steering wheel")
        (field (name "FRAME_USER") "Alexander Ulasik, Johannes Steininger")
      )
      (libsource (lib "eagle-import") (part "A4L-LOC-RACING-NOLOGO"))
    )
    (comp (ref "R34")
      (value "X(10k)")
      (footprint "eagle-import:R0805")
      (libsource (lib "eagle-import") (part "R-EU_R0805"))
    )
    (comp (ref "R35")
      (value "X(10k)")
      (footprint "eagle-import:R0805")
      (libsource (lib "eagle-import") (part "R-EU_R0805"))
    )
    (comp (ref "R36")
      (value "X(10k)")
      (footprint "eagle-import:R0805")
      (libsource (lib "eagle-import") (part "R-EU_R0805"))
    )
  )
  (nets
    (net (code "1") (name "+5V{slash}1#") (class "Default")
      (node (ref "C1") (pin "1") (pinfunction "1_1") (pintype "passive"))
      (node (ref "C10") (pin "1") (pinfunction "1_1") (pintype "passive"))
      (node (ref "C11") (pin "1") (pinfunction "1_1") (pintype "passive"))
      (node (ref "C12") (pin "2") (pinfunction "2_2") (pintype "passive"))
      (node (ref "C13") (pin "2") (pinfunction "2_2") (pintype "passive"))
      (node (ref "C15") (pin "1") (pinfunction "1_1") (pintype "passive"))
      (node (ref "C18") (pin "1") (pinfunction "1_1") (pintype "passive"))
      (node (ref "C21") (pin "1") (pinfunction "1_1") (pintype "passive"))
      (node (ref "C23") (pin "2") (pinfunction "2_2") (pintype "passive"))
      (node (ref "C24") (pin "2") (pinfunction "2_2") (pintype "passive"))
      (node (ref "C25") (pin "2") (pinfunction "2_2") (pintype "passive"))
      (node (ref "C26") (pin "2") (pinfunction "2_2") (pintype "passive"))
      (node (ref "C3") (pin "1") (pinfunction "1_1") (pintype "passive"))
      (node (ref "C30") (pin "2") (pinfunction "2_2") (pintype "passive"))
      (node (ref "C35") (pin "1") (pinfunction "1_1") (pintype "passive"))
      (node (ref "C36") (pin "+") (pinfunction "+_+") (pintype "passive"))
      (node (ref "C4") (pin "2") (pinfunction "2_2") (pintype "passive"))
      (node (ref "C40") (pin "1") (pinfunction "1_1") (pintype "passive"))
      (node (ref "C44") (pin "2") (pinfunction "2_2") (pintype "passive"))
      (node (ref "C45") (pin "2") (pinfunction "2_2") (pintype "passive"))
      (node (ref "C5") (pin "2") (pinfunction "2_2") (pintype "passive"))
      (node (ref "C6") (pin "2") (pinfunction "2_2") (pintype "passive"))
      (node (ref "C7") (pin "2") (pinfunction "2_2") (pintype "passive"))
      (node (ref "C8") (pin "2") (pinfunction "2_2") (pintype "passive"))
      (node (ref "C9") (pin "2") (pinfunction "2_2") (pintype "passive"))
      (node (ref "CON1") (pin "1") (pinfunction "P$1_1") (pintype "bidirectional"))
      (node (ref "DISPLAY") (pin "P$2") (pinfunction "VDD_P$2") (pintype "bidirectional"))
      (node (ref "DISPLAY") (pin "P$22") (pinfunction "VDD2_P$22") (pintype "bidirectional"))
      (node (ref "DISPLAY") (pin "P$5") (pinfunction "RESET_P$5") (pintype "bidirectional"))
      (node (ref "IC1") (pin "14") (pinfunction "VCCIOA_14") (pintype "bidirectional"))
      (node (ref "IC1") (pin "3") (pinfunction "VCC0_3") (pintype "bidirectional"))
      (node (ref "IC1") (pin "31") (pinfunction "VCCIOB_31") (pintype "bidirectional"))
      (node (ref "IC1") (pin "42") (pinfunction "VCC1_42") (pintype "bidirectional"))
      (node (ref "IC2") (pin "14") (pinfunction "VCC_14") (pintype "power_in"))
      (node (ref "IC3") (pin "20") (pinfunction "VCC_20") (pintype "power_in"))
      (node (ref "IC4") (pin "20") (pinfunction "VCC_20") (pintype "power_in"))
      (node (ref "IC5") (pin "19") (pinfunction "VCC_19") (pintype "power_in"))
      (node (ref "IC6") (pin "4") (pinfunction "FB_4") (pintype "bidirectional"))
      (node (ref "J1") (pin "19") (pinfunction "P$19_19") (pintype "passive"))
      (node (ref "J1") (pin "2") (pinfunction "P$2_2") (pintype "passive"))
      (node (ref "J1") (pin "8") (pinfunction "P$8_8") (pintype "passive"))
      (node (ref "L2") (pin "1") (pinfunction "1_1") (pintype "passive"))
      (node (ref "R10") (pin "1") (pinfunction "1_1") (pintype "passive"))
      (node (ref "R14") (pin "1") (pinfunction "1_1") (pintype "passive"))
      (node (ref "R16") (pin "1") (pinfunction "1_1") (pintype "passive"))
      (node (ref "R19") (pin "2") (pinfunction "2_2") (pintype "passive"))
      (node (ref "R20") (pin "2") (pinfunction "2_2") (pintype "passive"))
      (node (ref "R21") (pin "2") (pinfunction "2_2") (pintype "passive"))
      (node (ref "R22") (pin "2") (pinfunction "2_2") (pintype "passive"))
      (node (ref "R24") (pin "2") (pinfunction "2_2") (pintype "passive"))
      (node (ref "R3") (pin "2") (pinfunction "2_2") (pintype "passive"))
      (node (ref "R39") (pin "2") (pinfunction "2_2") (pintype "passive"))
      (node (ref "R4") (pin "1") (pinfunction "1_1") (pintype "passive"))
      (node (ref "R40") (pin "2") (pinfunction "2_2") (pintype "passive"))
      (node (ref "R5") (pin "2") (pinfunction "2_2") (pintype "passive"))
      (node (ref "R6") (pin "1") (pinfunction "1_1") (pintype "passive"))
      (node (ref "R7") (pin "1") (pinfunction "1_1") (pintype "passive"))
      (node (ref "R8") (pin "2") (pinfunction "2_2") (pintype "passive"))
      (node (ref "R9") (pin "2") (pinfunction "2_2") (pintype "passive"))
      (node (ref "U1") (pin "12") (pinfunction "VAREF_12") (pintype "input"))
      (node (ref "U1") (pin "16") (pinfunction "VDDPB_16") (pintype "power_in"))
      (node (ref "U1") (pin "18") (pinfunction "VDDPB_18") (pintype "power_in"))
      (node (ref "U1") (pin "2") (pinfunction "VDDPB_2") (pintype "power_in"))
      (node (ref "U1") (pin "32") (pinfunction "VDDPB_32") (pintype "power_in"))
      (node (ref "U1") (pin "34") (pinfunction "VDDPB_34") (pintype "power_in"))
      (node (ref "U1") (pin "48") (pinfunction "VDDPB_48") (pintype "power_in"))
      (node (ref "U1") (pin "50") (pinfunction "VDDPB_50") (pintype "power_in"))
      (node (ref "U1") (pin "64") (pinfunction "VDDPB_64") (pintype "power_in"))
      (node (ref "U1") (pin "9") (pinfunction "VDDPA_9") (pintype "power_in"))
      (node (ref "U2") (pin "3") (pinfunction "VCC_3") (pintype "power_in"))
    )
    (net (code "2") (name "BUTTON_PUSHED_1") (class "Default")
      (node (ref "IC3") (pin "11") (pinfunction "~{CH}_11") (pintype "output"))
      (node (ref "R14") (pin "2") (pinfunction "2_2") (pintype "passive"))
      (node (ref "U1") (pin "26") (pinfunction "P2.1_26") (pintype "bidirectional"))
    )
    (net (code "3") (name "BUTTON_PUSHED_2") (class "Default")
      (node (ref "R11") (pin "2") (pinfunction "2_2") (pintype "passive"))
      (node (ref "T3") (pin "1") (pinfunction "D_1") (pintype "passive"))
      (node (ref "U1") (pin "27") (pinfunction "P2.2_27") (pintype "bidirectional"))
    )
    (net (code "4") (name "BUT_MIN") (class "Default")
      (node (ref "IC3") (pin "16") (pinfunction "OUT4_16") (pintype "output"))
      (node (ref "U1") (pin "53") (pinfunction "P10.10_53") (pintype "bidirectional"))
    )
    (net (code "5") (name "BUT_PLUS") (class "Default")
      (node (ref "IC3") (pin "12") (pinfunction "OUT8_12") (pintype "output"))
      (node (ref "U1") (pin "56") (pinfunction "P10.13_56") (pintype "bidirectional"))
    )
    (net (code "6") (name "BUT_TL") (class "Default")
      (node (ref "IC3") (pin "14") (pinfunction "OUT6_14") (pintype "output"))
      (node (ref "U1") (pin "54") (pinfunction "P10.11_54") (pintype "bidirectional"))
    )
    (net (code "7") (name "CAN0_HIGH") (class "Default")
      (node (ref "D3") (pin "1") (pinfunction "C1_1") (pintype "passive"))
      (node (ref "J1") (pin "31") (pinfunction "P$31_31") (pintype "bidirectional"))
      (node (ref "L1") (pin "3") (pinfunction "3_3") (pintype "passive"))
      (node (ref "R1") (pin "1") (pinfunction "1_1") (pintype "passive"))
    )
    (net (code "8") (name "CAN0_LOW") (class "Default")
      (node (ref "D2") (pin "2") (pinfunction "C2_2") (pintype "passive"))
      (node (ref "J1") (pin "29") (pinfunction "P$29_29") (pintype "passive"))
      (node (ref "L1") (pin "2") (pinfunction "2_2") (pintype "passive"))
      (node (ref "R2") (pin "1") (pinfunction "1_1") (pintype "passive"))
    )
    (net (code "9") (name "CAN0_RXD") (class "Default")
      (node (ref "U1") (pin "31") (pinfunction "P2.6_31") (pintype "bidirectional"))
      (node (ref "U2") (pin "4") (pinfunction "RXD_4") (pintype "output"))
    )
    (net (code "10") (name "CAN0_TXD") (class "Default")
      (node (ref "U1") (pin "30") (pinfunction "P2.5_30") (pintype "bidirectional"))
      (node (ref "U2") (pin "1") (pinfunction "TXD_1") (pintype "input"))
    )
    (net (code "11") (name "DAP0") (class "Default")
      (node (ref "CON1") (pin "4") (pinfunction "P$4_4") (pintype "bidirectional"))
      (node (ref "J1") (pin "11") (pinfunction "P$11_11") (pintype "passive"))
      (node (ref "U1") (pin "37") (pinfunction "P2.9_37") (pintype "bidirectional"))
    )
    (net (code "12") (name "DAP1") (class "Default")
      (node (ref "CON1") (pin "2") (pinfunction "P$2_2") (pintype "bidirectional"))
      (node (ref "J1") (pin "13") (pinfunction "P$13_13") (pintype "passive"))
      (node (ref "U1") (pin "5") (pinfunction "P7.0_5") (pintype "bidirectional"))
    )
    (net (code "13") (name "DD_5") (class "Default")
      (node (ref "IC4") (pin "14") (pinfunction "OUT6_14") (pintype "output"))
      (node (ref "U1") (pin "46") (pinfunction "P10.6_46") (pintype "bidirectional"))
    )
    (net (code "14") (name "DD_PIN3") (class "Default")
      (node (ref "J1") (pin "1") (pinfunction "P$1_1") (pintype "passive"))
      (node (ref "T3") (pin "3") (pinfunction "G_3") (pintype "passive"))
      (node (ref "U1") (pin "44") (pinfunction "P10.4_44") (pintype "bidirectional"))
    )
    (net (code "15") (name "DD_PIN4") (class "Default")
      (node (ref "J1") (pin "3") (pinfunction "P$3_3") (pintype "passive"))
      (node (ref "U1") (pin "45") (pinfunction "P10.5_45") (pintype "bidirectional"))
    )
    (net (code "16") (name "DD_PIN5") (class "Default")
      (node (ref "IC4") (pin "7") (pinfunction "IN6_7") (pintype "input"))
      (node (ref "J1") (pin "5") (pinfunction "P$5_5") (pintype "passive"))
    )
    (net (code "17") (name "DIG0") (class "Default")
      (node (ref "IC5") (pin "2") (pinfunction "DIG0_2") (pintype "output"))
      (node (ref "J1") (pin "24") (pinfunction "P$24_24") (pintype "passive"))
    )
    (net (code "18") (name "DIG1") (class "Default")
      (node (ref "IC5") (pin "11") (pinfunction "DIG1_11") (pintype "output"))
      (node (ref "J1") (pin "26") (pinfunction "P$26_26") (pintype "passive"))
    )
    (net (code "19") (name "DIG2") (class "Default")
      (node (ref "IC5") (pin "6") (pinfunction "DIG2_6") (pintype "output"))
      (node (ref "J1") (pin "28") (pinfunction "P$28_28") (pintype "passive"))
    )
    (net (code "20") (name "EEDATA") (class "Default")
      (node (ref "IC1") (pin "2") (pinfunction "EEDATA_2") (pintype "bidirectional"))
      (node (ref "R24") (pin "1") (pinfunction "1_1") (pintype "passive"))
    )
    (net (code "21") (name "ENCODER_1") (class "Default")
      (node (ref "IC4") (pin "3") (pinfunction "IN2_3") (pintype "input"))
      (node (ref "J1") (pin "40") (pinfunction "P$40_40") (pintype "bidirectional"))
    )
    (net (code "22") (name "ENCODER_2") (class "Default")
      (node (ref "IC4") (pin "4") (pinfunction "IN3_4") (pintype "input"))
      (node (ref "J1") (pin "38") (pinfunction "P$38_38") (pintype "bidirectional"))
    )
    (net (code "23") (name "ENCODER_4") (class "Default")
      (node (ref "IC4") (pin "5") (pinfunction "IN4_5") (pintype "input"))
      (node (ref "J1") (pin "37") (pinfunction "P$37_37") (pintype "bidirectional"))
    )
    (net (code "24") (name "ENCODER_8") (class "Default")
      (node (ref "IC4") (pin "6") (pinfunction "IN5_6") (pintype "input"))
      (node (ref "J1") (pin "39") (pinfunction "P$39_39") (pintype "bidirectional"))
    )
    (net (code "25") (name "ENC_1") (class "Default")
      (node (ref "IC4") (pin "18") (pinfunction "OUT2_18") (pintype "output"))
      (node (ref "U1") (pin "19") (pinfunction "P5.4_19") (pintype "bidirectional"))
    )
    (net (code "26") (name "ENC_2") (class "Default")
      (node (ref "IC4") (pin "17") (pinfunction "OUT3_17") (pintype "output"))
      (node (ref "U1") (pin "20") (pinfunction "P5.8_20") (pintype "bidirectional"))
    )
    (net (code "27") (name "ENC_4") (class "Default")
      (node (ref "IC4") (pin "16") (pinfunction "OUT4_16") (pintype "output"))
      (node (ref "U1") (pin "21") (pinfunction "P5.10_21") (pintype "bidirectional"))
    )
    (net (code "28") (name "ENC_8") (class "Default")
      (node (ref "IC4") (pin "15") (pinfunction "OUT5_15") (pintype "output"))
      (node (ref "U1") (pin "22") (pinfunction "P5.13_22") (pintype "bidirectional"))
    )
    (net (code "29") (name "EN_PB_1") (class "Default")
      (node (ref "IC3") (pin "1") (pinfunction "~{EN}_1") (pintype "input"))
      (node (ref "R6") (pin "2") (pinfunction "2_2") (pintype "passive"))
      (node (ref "U1") (pin "25") (pinfunction "P2.0_25") (pintype "bidirectional"))
    )
    (net (code "30") (name "EN_PB_2") (class "Default")
      (node (ref "IC4") (pin "1") (pinfunction "~{EN}_1") (pintype "input"))
      (node (ref "R10") (pin "2") (pinfunction "2_2") (pintype "passive"))
      (node (ref "U1") (pin "42") (pinfunction "P2.10_42") (pintype "bidirectional"))
    )
    (net (code "31") (name "GND") (class "Default")
      (node (ref "C1") (pin "2") (pinfunction "2_2") (pintype "passive"))
      (node (ref "C10") (pin "2") (pinfunction "2_2") (pintype "passive"))
      (node (ref "C11") (pin "2") (pinfunction "2_2") (pintype "passive"))
      (node (ref "C12") (pin "1") (pinfunction "1_1") (pintype "passive"))
      (node (ref "C13") (pin "1") (pinfunction "1_1") (pintype "passive"))
      (node (ref "C14") (pin "1") (pinfunction "1_1") (pintype "passive"))
      (node (ref "C15") (pin "2") (pinfunction "2_2") (pintype "passive"))
      (node (ref "C16") (pin "2") (pinfunction "2_2") (pintype "passive"))
      (node (ref "C17") (pin "2") (pinfunction "2_2") (pintype "passive"))
      (node (ref "C18") (pin "2") (pinfunction "2_2") (pintype "passive"))
      (node (ref "C19") (pin "2") (pinfunction "2_2") (pintype "passive"))
      (node (ref "C2") (pin "2") (pinfunction "2_2") (pintype "passive"))
      (node (ref "C20") (pin "1") (pinfunction "1_1") (pintype "passive"))
      (node (ref "C21") (pin "2") (pinfunction "2_2") (pintype "passive"))
      (node (ref "C22") (pin "1") (pinfunction "1_1") (pintype "passive"))
      (node (ref "C23") (pin "1") (pinfunction "1_1") (pintype "passive"))
      (node (ref "C24") (pin "1") (pinfunction "1_1") (pintype "passive"))
      (node (ref "C25") (pin "1") (pinfunction "1_1") (pintype "passive"))
      (node (ref "C26") (pin "1") (pinfunction "1_1") (pintype "passive"))
      (node (ref "C27") (pin "1") (pinfunction "1_1") (pintype "passive"))
      (node (ref "C28") (pin "2") (pinfunction "2_2") (pintype "passive"))
      (node (ref "C29") (pin "2") (pinfunction "2_2") (pintype "passive"))
      (node (ref "C3") (pin "2") (pinfunction "2_2") (pintype "passive"))
      (node (ref "C30") (pin "1") (pinfunction "1_1") (pintype "passive"))
      (node (ref "C31") (pin "2") (pinfunction "2_2") (pintype "passive"))
      (node (ref "C32") (pin "1") (pinfunction "1_1") (pintype "passive"))
      (node (ref "C33") (pin "1") (pinfunction "1_1") (pintype "passive"))
      (node (ref "C34") (pin "2") (pinfunction "2_2") (pintype "passive"))
      (node (ref "C35") (pin "2") (pinfunction "2_2") (pintype "passive"))
      (node (ref "C36") (pin "-") (pinfunction "-_-") (pintype "passive"))
      (node (ref "C37") (pin "-") (pinfunction "-_-") (pintype "passive"))
      (node (ref "C38") (pin "-") (pinfunction "-_-") (pintype "passive"))
      (node (ref "C39") (pin "1") (pinfunction "1_1") (pintype "passive"))
      (node (ref "C4") (pin "1") (pinfunction "1_1") (pintype "passive"))
      (node (ref "C40") (pin "2") (pinfunction "2_2") (pintype "passive"))
      (node (ref "C41") (pin "1") (pinfunction "1_1") (pintype "passive"))
      (node (ref "C44") (pin "1") (pinfunction "1_1") (pintype "passive"))
      (node (ref "C45") (pin "1") (pinfunction "1_1") (pintype "passive"))
      (node (ref "C5") (pin "1") (pinfunction "1_1") (pintype "passive"))
      (node (ref "C6") (pin "1") (pinfunction "1_1") (pintype "passive"))
      (node (ref "C7") (pin "1") (pinfunction "1_1") (pintype "passive"))
      (node (ref "C8") (pin "1") (pinfunction "1_1") (pintype "passive"))
      (node (ref "C9") (pin "1") (pinfunction "1_1") (pintype "passive"))
      (node (ref "CON1") (pin "3") (pinfunction "P$3_3") (pintype "bidirectional"))
      (node (ref "CON1") (pin "5") (pinfunction "P$5_5") (pintype "bidirectional"))
      (node (ref "CON1") (pin "9") (pinfunction "P$9_9") (pintype "bidirectional"))
      (node (ref "D1") (pin "A") (pinfunction "A_A") (pintype "passive"))
      (node (ref "D2") (pin "1") (pinfunction "C1_1") (pintype "passive"))
      (node (ref "D3") (pin "2") (pinfunction "C2_2") (pintype "passive"))
      (node (ref "D5") (pin "A") (pinfunction "A_A") (pintype "passive"))
      (node (ref "DISPLAY") (pin "P$1") (pinfunction "GND_P$1") (pintype "bidirectional"))
      (node (ref "DISPLAY") (pin "P$21") (pinfunction "GND2_P$21") (pintype "bidirectional"))
      (node (ref "IC1") (pin "18") (pinfunction "GND1_18") (pintype "bidirectional"))
      (node (ref "IC1") (pin "25") (pinfunction "GND2_25") (pintype "bidirectional"))
      (node (ref "IC1") (pin "34") (pinfunction "GND3_34") (pintype "bidirectional"))
      (node (ref "IC1") (pin "45") (pinfunction "AGND_45") (pintype "bidirectional"))
      (node (ref "IC1") (pin "47") (pinfunction "TEST_47") (pintype "bidirectional"))
      (node (ref "IC1") (pin "9") (pinfunction "GND0_9") (pintype "bidirectional"))
      (node (ref "IC2") (pin "7") (pinfunction "GND_7") (pintype "power_in"))
      (node (ref "IC3") (pin "10") (pinfunction "GND_10") (pintype "power_in"))
      (node (ref "IC4") (pin "10") (pinfunction "GND_10") (pintype "power_in"))
      (node (ref "IC5") (pin "4") (pinfunction "GND_4") (pintype "power_in"))
      (node (ref "IC5") (pin "9") (pinfunction "GND_9") (pintype "power_in"))
      (node (ref "IC6") (pin "1") (pinfunction "SYNC_1") (pintype "bidirectional"))
      (node (ref "IC6") (pin "2") (pinfunction "GND1_2") (pintype "bidirectional"))
      (node (ref "IC6") (pin "HS") (pinfunction "GND2_HS") (pintype "bidirectional"))
      (node (ref "J1") (pin "12") (pinfunction "P$12_12") (pintype "passive"))
      (node (ref "J1") (pin "21") (pinfunction "P$21_21") (pintype "passive"))
      (node (ref "J1") (pin "30") (pinfunction "P$30_30") (pintype "passive"))
      (node (ref "J1") (pin "33") (pinfunction "P$33_33") (pintype "bidirectional"))
      (node (ref "J1") (pin "4") (pinfunction "P$4_4") (pintype "passive"))
      (node (ref "J1") (pin "6") (pinfunction "P$6_6") (pintype "passive"))
      (node (ref "R12") (pin "2") (pinfunction "2_2") (pintype "passive"))
      (node (ref "R13") (pin "2") (pinfunction "2_2") (pintype "passive"))
      (node (ref "R15") (pin "1") (pinfunction "1_1") (pintype "passive"))
      (node (ref "R17") (pin "1") (pinfunction "1_1") (pintype "passive"))
      (node (ref "R18") (pin "1") (pinfunction "1_1") (pintype "passive"))
      (node (ref "R23") (pin "2") (pinfunction "2_2") (pintype "passive"))
      (node (ref "R26") (pin "1") (pinfunction "1_1") (pintype "passive"))
      (node (ref "R32") (pin "2") (pinfunction "2_2") (pintype "passive"))
      (node (ref "R33") (pin "2") (pinfunction "2_2") (pintype "passive"))
      (node (ref "R34") (pin "1") (pinfunction "1_1") (pintype "passive"))
      (node (ref "R35") (pin "1") (pinfunction "1_1") (pintype "passive"))
      (node (ref "R36") (pin "1") (pinfunction "1_1") (pintype "passive"))
      (node (ref "R37") (pin "1") (pinfunction "1_1") (pintype "passive"))
      (node (ref "R38") (pin "1") (pinfunction "1_1") (pintype "passive"))
      (node (ref "T3") (pin "2") (pinfunction "S_2") (pintype "passive"))
      (node (ref "U1") (pin "1") (pinfunction "GND_1") (pintype "power_in"))
      (node (ref "U1") (pin "13") (pinfunction "AGND_13") (pintype "power_in"))
      (node (ref "U1") (pin "17") (pinfunction "GND_17") (pintype "power_in"))
      (node (ref "U1") (pin "33") (pinfunction "GND_33") (pintype "power_in"))
      (node (ref "U1") (pin "49") (pinfunction "GND_49") (pintype "power_in"))
      (node (ref "U1") (pin "PAD") (pinfunction "PAD_PAD") (pintype "power_in"))
      (node (ref "U2") (pin "2") (pinfunction "GND_2") (pintype "power_in"))
      (node (ref "U2") (pin "8") (pinfunction "STB_8") (pintype "input"))
    )
    (net (code "32") (name "LVPD_SUP") (class "Default")
      (node (ref "J1") (pin "35") (pinfunction "P$35_35") (pintype "bidirectional"))
      (node (ref "T1") (pin "2") (pinfunction "D_2") (pintype "passive"))
      (node (ref "T1") (pin "TAB") (pinfunction "D_TAB") (pintype "passive"))
    )
    (net (code "33") (name "MINUS") (class "Default")
      (node (ref "IC3") (pin "5") (pinfunction "IN4_5") (pintype "input"))
      (node (ref "J1") (pin "34") (pinfunction "P$34_34") (pintype "bidirectional"))
    )
    (net (code "34") (name "Net-(C2-Pad1)") (class "Default")
      (node (ref "C2") (pin "1") (pinfunction "1_1") (pintype "passive"))
      (node (ref "JP1") (pin "2") (pinfunction "2_2") (pintype "passive"))
      (node (ref "R1") (pin "2") (pinfunction "2_2") (pintype "passive"))
      (node (ref "R2") (pin "2") (pinfunction "2_2") (pintype "passive"))
    )
    (net (code "35") (name "Net-(C16-Pad1)") (class "Default")
      (node (ref "C16") (pin "1") (pinfunction "1_1") (pintype "passive"))
      (node (ref "C17") (pin "1") (pinfunction "1_1") (pintype "passive"))
      (node (ref "C19") (pin "1") (pinfunction "1_1") (pintype "passive"))
      (node (ref "U1") (pin "24") (pinfunction "VDDI1_24") (pintype "power_in"))
      (node (ref "U1") (pin "41") (pinfunction "VDDI1_41") (pintype "power_in"))
      (node (ref "U1") (pin "57") (pinfunction "VDDI1_57") (pintype "power_in"))
    )
    (net (code "36") (name "Net-(C43-Pad1)") (class "Default")
      (node (ref "C43") (pin "1") (pinfunction "1_1") (pintype "passive"))
      (node (ref "R38") (pin "2") (pinfunction "2_2") (pintype "passive"))
    )
    (net (code "37") (name "Net-(DISPLAY-BAUD0(SS))") (class "Default")
      (node (ref "DISPLAY") (pin "P$6") (pinfunction "BAUD0(SS)_P$6") (pintype "bidirectional"))
      (node (ref "R36") (pin "2") (pinfunction "2_2") (pintype "passive"))
    )
    (net (code "38") (name "Net-(DISPLAY-BAUD1(MOSI))") (class "Default")
      (node (ref "DISPLAY") (pin "P$7") (pinfunction "BAUD1(MOSI)_P$7") (pintype "bidirectional"))
      (node (ref "R35") (pin "2") (pinfunction "2_2") (pintype "passive"))
    )
    (net (code "39") (name "Net-(DISPLAY-BAUD2(MISO))") (class "Default")
      (node (ref "DISPLAY") (pin "P$8") (pinfunction "BAUD2(MISO)_P$8") (pintype "bidirectional"))
      (node (ref "R34") (pin "2") (pinfunction "2_2") (pintype "passive"))
    )
    (net (code "40") (name "Net-(IC1-3V3OUT)") (class "Default")
      (node (ref "C14") (pin "2") (pinfunction "2_2") (pintype "passive"))
      (node (ref "IC1") (pin "6") (pinfunction "3V3OUT_6") (pintype "bidirectional"))
    )
    (net (code "41") (name "Net-(IC1-ADBUS0)") (class "Default")
      (node (ref "IC1") (pin "24") (pinfunction "ADBUS0_24") (pintype "bidirectional"))
      (node (ref "R31") (pin "1") (pinfunction "1_1") (pintype "passive"))
    )
    (net (code "42") (name "Net-(IC1-ADBUS1)") (class "Default")
      (node (ref "IC1") (pin "23") (pinfunction "ADBUS1_23") (pintype "bidirectional"))
      (node (ref "R30") (pin "1") (pinfunction "1_1") (pintype "passive"))
    )
    (net (code "43") (name "Net-(IC1-AVVC)") (class "Default")
      (node (ref "C27") (pin "2") (pinfunction "2_2") (pintype "passive"))
      (node (ref "IC1") (pin "46") (pinfunction "AVVC_46") (pintype "bidirectional"))
      (node (ref "R20") (pin "1") (pinfunction "1_1") (pintype "passive"))
    )
    (net (code "44") (name "Net-(IC1-RSTOUT#)") (class "Default")
      (node (ref "IC1") (pin "5") (pinfunction "RSTOUT#_5") (pintype "bidirectional"))
      (node (ref "R27") (pin "2") (pinfunction "2_2") (pintype "passive"))
    )
    (net (code "45") (name "Net-(IC1-USBDM)") (class "Default")
      (node (ref "IC1") (pin "8") (pinfunction "USBDM_8") (pintype "bidirectional"))
      (node (ref "R29") (pin "2") (pinfunction "2_2") (pintype "passive"))
    )
    (net (code "46") (name "Net-(IC1-USBDP)") (class "Default")
      (node (ref "IC1") (pin "7") (pinfunction "USBDP_7") (pintype "bidirectional"))
      (node (ref "R27") (pin "1") (pinfunction "1_1") (pintype "passive"))
      (node (ref "R28") (pin "2") (pinfunction "2_2") (pintype "passive"))
    )
    (net (code "47") (name "Net-(IC1-XTIN)") (class "Default")
      (node (ref "C32") (pin "2") (pinfunction "2_2") (pintype "passive"))
      (node (ref "IC1") (pin "43") (pinfunction "XTIN_43") (pintype "bidirectional"))
      (node (ref "Q1") (pin "2") (pinfunction "2_2") (pintype "passive"))
    )
    (net (code "48") (name "Net-(IC1-XTOUT)") (class "Default")
      (node (ref "C33") (pin "2") (pinfunction "2_2") (pintype "passive"))
      (node (ref "IC1") (pin "44") (pinfunction "XTOUT_44") (pintype "bidirectional"))
      (node (ref "Q1") (pin "1") (pinfunction "1_1") (pintype "passive"))
    )
    (net (code "49") (name "Net-(IC2A-I)") (class "Default")
      (node (ref "IC2") (pin "1") (pinfunction "OE_1") (pintype "input"))
      (node (ref "IC2") (pin "2") (pinfunction "I_2") (pintype "input"))
      (node (ref "IC2") (pin "4") (pinfunction "OE_4") (pintype "input"))
      (node (ref "IC2") (pin "5") (pinfunction "I_5") (pintype "input"))
      (node (ref "R13") (pin "1") (pinfunction "1_1") (pintype "passive"))
    )
    (net (code "50") (name "Net-(IC3-IN1)") (class "Default")
      (node (ref "IC3") (pin "2") (pinfunction "IN1_2") (pintype "input"))
      (node (ref "R7") (pin "2") (pinfunction "2_2") (pintype "passive"))
    )
    (net (code "51") (name "Net-(IC3-IN2)") (class "Default")
      (node (ref "IC3") (pin "3") (pinfunction "IN2_3") (pintype "input"))
      (node (ref "R8") (pin "1") (pinfunction "1_1") (pintype "passive"))
    )
    (net (code "52") (name "Net-(IC3-IN3)") (class "Default")
      (node (ref "IC3") (pin "4") (pinfunction "IN3_4") (pintype "input"))
      (node (ref "R9") (pin "1") (pinfunction "1_1") (pintype "passive"))
    )
    (net (code "53") (name "Net-(IC4-IN1)") (class "Default")
      (node (ref "IC4") (pin "2") (pinfunction "IN1_2") (pintype "input"))
      (node (ref "R3") (pin "1") (pinfunction "1_1") (pintype "passive"))
    )
    (net (code "54") (name "Net-(IC4-IN7)") (class "Default")
      (node (ref "IC4") (pin "8") (pinfunction "IN7_8") (pintype "input"))
      (node (ref "R39") (pin "1") (pinfunction "1_1") (pintype "passive"))
    )
    (net (code "55") (name "Net-(IC4-IN8)") (class "Default")
      (node (ref "IC4") (pin "9") (pinfunction "IN8_9") (pintype "input"))
      (node (ref "R40") (pin "1") (pinfunction "1_1") (pintype "passive"))
    )
    (net (code "56") (name "Net-(IC4-~{CH})") (class "Default")
      (node (ref "IC4") (pin "11") (pinfunction "~{CH}_11") (pintype "output"))
      (node (ref "R11") (pin "1") (pinfunction "1_1") (pintype "passive"))
    )
    (net (code "57") (name "Net-(IC5-ISET)") (class "Default")
      (node (ref "IC5") (pin "18") (pinfunction "ISET_18") (pintype "input"))
      (node (ref "R4") (pin "2") (pinfunction "2_2") (pintype "passive"))
    )
    (net (code "58") (name "Net-(IC6-BDS)") (class "Default")
      (node (ref "C42") (pin "1") (pinfunction "1_1") (pintype "passive"))
      (node (ref "IC6") (pin "5") (pinfunction "BDS_5") (pintype "bidirectional"))
    )
    (net (code "59") (name "Net-(IC6-BUO)") (class "Default")
      (node (ref "C42") (pin "2") (pinfunction "2_2") (pintype "passive"))
      (node (ref "D1") (pin "C") (pinfunction "C_C") (pintype "passive"))
      (node (ref "IC6") (pin "6") (pinfunction "BUO_6") (pintype "bidirectional"))
      (node (ref "L2") (pin "2") (pinfunction "2_2") (pintype "passive"))
    )
    (net (code "60") (name "Net-(IC6-COMP)") (class "Default")
      (node (ref "C43") (pin "2") (pinfunction "2_2") (pintype "passive"))
      (node (ref "IC6") (pin "3") (pinfunction "COMP_3") (pintype "bidirectional"))
    )
    (net (code "61") (name "Net-(IC6-EN)") (class "Default")
      (node (ref "C37") (pin "+") (pinfunction "+_+") (pintype "passive"))
      (node (ref "C38") (pin "+") (pinfunction "+_+") (pintype "passive"))
      (node (ref "C39") (pin "2") (pinfunction "2_2") (pintype "passive"))
      (node (ref "IC6") (pin "7") (pinfunction "EN_7") (pintype "bidirectional"))
      (node (ref "IC6") (pin "8") (pinfunction "VS_8") (pintype "bidirectional"))
      (node (ref "L3") (pin "2") (pinfunction "2_2") (pintype "passive"))
    )
    (net (code "62") (name "Net-(LED1-PadC)") (class "Default")
      (node (ref "LED1") (pin "C") (pinfunction "C_C") (pintype "passive"))
      (node (ref "R12") (pin "1") (pinfunction "1_1") (pintype "passive"))
    )
    (net (code "63") (name "Net-(LED2-PadC)") (class "Default")
      (node (ref "LED2") (pin "C") (pinfunction "C_C") (pintype "passive"))
      (node (ref "R33") (pin "1") (pinfunction "1_1") (pintype "passive"))
    )
    (net (code "64") (name "Net-(LED3-PadC)") (class "Default")
      (node (ref "LED3") (pin "C") (pinfunction "C_C") (pintype "passive"))
      (node (ref "R32") (pin "1") (pinfunction "1_1") (pintype "passive"))
    )
    (net (code "65") (name "Net-(Q2-2)") (class "Default")
      (node (ref "C34") (pin "1") (pinfunction "1_1") (pintype "passive"))
      (node (ref "Q2") (pin "3") (pinfunction "2_3") (pintype "bidirectional"))
      (node (ref "U1") (pin "60") (pinfunction "XTAL2_60") (pintype "output"))
    )
    (net (code "66") (name "Net-(T1-G)") (class "Default")
      (node (ref "D4") (pin "A") (pinfunction "A_A") (pintype "passive"))
      (node (ref "R37") (pin "2") (pinfunction "2_2") (pintype "passive"))
      (node (ref "T1") (pin "1") (pinfunction "G_1") (pintype "passive"))
    )
    (net (code "67") (name "Net-(T1-S)") (class "Default")
      (node (ref "C41") (pin "2") (pinfunction "2_2") (pintype "passive"))
      (node (ref "D4") (pin "C") (pinfunction "C_C") (pintype "passive"))
      (node (ref "D5") (pin "C") (pinfunction "C_C") (pintype "passive"))
      (node (ref "L3") (pin "1") (pinfunction "1_1") (pintype "passive"))
      (node (ref "T1") (pin "3") (pinfunction "S_3") (pintype "passive"))
    )
    (net (code "68") (name "Net-(U1A-P10.0)") (class "Default")
      (node (ref "R16") (pin "2") (pinfunction "2_2") (pintype "passive"))
      (node (ref "U1") (pin "38") (pinfunction "P10.0_38") (pintype "bidirectional"))
    )
    (net (code "69") (name "Net-(U1A-P10.1)") (class "Default")
      (node (ref "LED2") (pin "A") (pinfunction "A_A") (pintype "passive"))
      (node (ref "R15") (pin "2") (pinfunction "2_2") (pintype "passive"))
      (node (ref "U1") (pin "39") (pinfunction "P10.1_39") (pintype "bidirectional"))
    )
    (net (code "70") (name "Net-(U1A-P10.2)") (class "Default")
      (node (ref "LED1") (pin "A") (pinfunction "A_A") (pintype "passive"))
      (node (ref "R17") (pin "2") (pinfunction "2_2") (pintype "passive"))
      (node (ref "U1") (pin "40") (pinfunction "P10.2_40") (pintype "bidirectional"))
    )
    (net (code "71") (name "Net-(U1A-P10.3)") (class "Default")
      (node (ref "LED3") (pin "A") (pinfunction "A_A") (pintype "passive"))
      (node (ref "R18") (pin "2") (pinfunction "2_2") (pintype "passive"))
      (node (ref "U1") (pin "43") (pinfunction "P10.3_43") (pintype "bidirectional"))
    )
    (net (code "72") (name "Net-(U1A-XTAL1)") (class "Default")
      (node (ref "C31") (pin "1") (pinfunction "1_1") (pintype "passive"))
      (node (ref "Q2") (pin "1") (pinfunction "1_1") (pintype "bidirectional"))
      (node (ref "U1") (pin "61") (pinfunction "XTAL1_61") (pintype "input"))
    )
    (net (code "73") (name "Net-(U1A-~{ESR0})") (class "Default")
      (node (ref "C22") (pin "2") (pinfunction "2_2") (pintype "passive"))
      (node (ref "R21") (pin "1") (pinfunction "1_1") (pintype "passive"))
      (node (ref "U1") (pin "63") (pinfunction "~{ESR0}_63") (pintype "bidirectional"))
    )
    (net (code "74") (name "Net-(U1A-~{TESTM})") (class "Default")
      (node (ref "R22") (pin "1") (pinfunction "1_1") (pintype "passive"))
      (node (ref "U1") (pin "3") (pinfunction "~{TESTM}_3") (pintype "input"))
    )
    (net (code "75") (name "Net-(U1B-VDDIM)") (class "Default")
      (node (ref "C28") (pin "1") (pinfunction "1_1") (pintype "passive"))
      (node (ref "C29") (pin "1") (pinfunction "1_1") (pintype "passive"))
      (node (ref "U1") (pin "6") (pinfunction "VDDIM_6") (pintype "power_in"))
    )
    (net (code "76") (name "Net-(U2-CANH)") (class "Default")
      (node (ref "L1") (pin "4") (pinfunction "4_4") (pintype "passive"))
      (node (ref "U2") (pin "7") (pinfunction "CANH_7") (pintype "bidirectional"))
    )
    (net (code "77") (name "Net-(U2-CANL)") (class "Default")
      (node (ref "L1") (pin "1") (pinfunction "1_1") (pintype "passive"))
      (node (ref "U2") (pin "6") (pinfunction "CANL_6") (pintype "bidirectional"))
    )
    (net (code "78") (name "Net-(U2-SPLIT)") (class "Default")
      (node (ref "JP1") (pin "1") (pinfunction "1_1") (pintype "passive"))
      (node (ref "U2") (pin "5") (pinfunction "SPLIT_5") (pintype "output"))
    )
    (net (code "79") (name "PLUS") (class "Default")
      (node (ref "IC3") (pin "9") (pinfunction "IN8_9") (pintype "input"))
      (node (ref "J1") (pin "10") (pinfunction "P$10_10") (pintype "passive"))
    )
    (net (code "80") (name "POTI_1") (class "Default")
      (node (ref "J1") (pin "7") (pinfunction "P$7_7") (pintype "passive"))
      (node (ref "U1") (pin "14") (pinfunction "P5.0_14") (pintype "bidirectional"))
    )
    (net (code "81") (name "RXD_DISP") (class "Default")
      (node (ref "DISPLAY") (pin "P$10") (pinfunction "RXD(DORD)_P$10") (pintype "bidirectional"))
      (node (ref "IC2") (pin "11") (pinfunction "O_11") (pintype "tri_state"))
      (node (ref "R31") (pin "2") (pinfunction "2_2") (pintype "passive"))
    )
    (net (code "82") (name "SEG_A") (class "Default")
      (node (ref "IC5") (pin "14") (pinfunction "SEGA_14") (pintype "output"))
      (node (ref "J1") (pin "14") (pinfunction "P$14_14") (pintype "passive"))
    )
    (net (code "83") (name "SEG_B") (class "Default")
      (node (ref "IC5") (pin "16") (pinfunction "SEGB_16") (pintype "output"))
      (node (ref "J1") (pin "16") (pinfunction "P$16_16") (pintype "passive"))
    )
    (net (code "84") (name "SEG_C") (class "Default")
      (node (ref "IC5") (pin "20") (pinfunction "SEGC_20") (pintype "output"))
      (node (ref "J1") (pin "18") (pinfunction "P$18_18") (pintype "passive"))
    )
    (net (code "85") (name "SEG_D") (class "Default")
      (node (ref "IC5") (pin "23") (pinfunction "SEGD_23") (pintype "output"))
      (node (ref "J1") (pin "20") (pinfunction "P$20_20") (pintype "passive"))
    )
    (net (code "86") (name "SEG_E") (class "Default")
      (node (ref "IC5") (pin "21") (pinfunction "SEGE_21") (pintype "output"))
      (node (ref "J1") (pin "22") (pinfunction "P$22_22") (pintype "passive"))
    )
    (net (code "87") (name "SHIFT_DOWN") (class "Default")
      (node (ref "IC3") (pin "6") (pinfunction "IN5_6") (pintype "input"))
      (node (ref "J1") (pin "36") (pinfunction "P$36_36") (pintype "bidirectional"))
    )
    (net (code "88") (name "SHIFT_UP") (class "Default")
      (node (ref "IC3") (pin "8") (pinfunction "IN7_8") (pintype "input"))
      (node (ref "J1") (pin "9") (pinfunction "P$9_9") (pintype "passive"))
    )
    (net (code "89") (name "SH_DN") (class "Default")
      (node (ref "IC3") (pin "15") (pinfunction "OUT5_15") (pintype "output"))
      (node (ref "U1") (pin "52") (pinfunction "P10.9_52") (pintype "bidirectional"))
    )
    (net (code "90") (name "SH_UP") (class "Default")
      (node (ref "IC3") (pin "13") (pinfunction "OUT7_13") (pintype "output"))
      (node (ref "U1") (pin "55") (pinfunction "P10.12_55") (pintype "bidirectional"))
    )
    (net (code "91") (name "TOP_LEFT") (class "Default")
      (node (ref "IC3") (pin "7") (pinfunction "IN6_7") (pintype "input"))
      (node (ref "J1") (pin "32") (pinfunction "P$32_32") (pintype "bidirectional"))
    )
    (net (code "92") (name "TXD_DISP") (class "Default")
      (node (ref "DISPLAY") (pin "P$11") (pinfunction "TXD(SPIMO)_P$11") (pintype "bidirectional"))
      (node (ref "IC2") (pin "9") (pinfunction "I_9") (pintype "input"))
      (node (ref "R30") (pin "2") (pinfunction "2_2") (pintype "passive"))
    )
    (net (code "93") (name "U0C0_RXD") (class "Default")
      (node (ref "IC2") (pin "8") (pinfunction "O_8") (pintype "tri_state"))
      (node (ref "U1") (pin "29") (pinfunction "P2.4_29") (pintype "bidirectional"))
    )
    (net (code "94") (name "U0C0_TXD") (class "Default")
      (node (ref "IC2") (pin "12") (pinfunction "I_12") (pintype "input"))
      (node (ref "U1") (pin "28") (pinfunction "P2.3_28") (pintype "bidirectional"))
    )
    (net (code "95") (name "U0C1_CLK") (class "Default")
      (node (ref "IC5") (pin "13") (pinfunction "CLK_13") (pintype "input"))
      (node (ref "U1") (pin "36") (pinfunction "P2.8_36") (pintype "bidirectional"))
    )
    (net (code "96") (name "U0C1_TXD") (class "Default")
      (node (ref "IC5") (pin "1") (pinfunction "DIN_1") (pintype "input"))
      (node (ref "U1") (pin "59") (pinfunction "P10.15_59") (pintype "bidirectional"))
    )
    (net (code "97") (name "USB_2") (class "Default")
      (node (ref "J1") (pin "25") (pinfunction "P$25_25") (pintype "passive"))
      (node (ref "R29") (pin "1") (pinfunction "1_1") (pintype "passive"))
    )
    (net (code "98") (name "USB_3") (class "Default")
      (node (ref "J1") (pin "23") (pinfunction "P$23_23") (pintype "passive"))
      (node (ref "R28") (pin "1") (pinfunction "1_1") (pintype "passive"))
    )
    (net (code "99") (name "USB_PWR") (class "Default")
      (node (ref "IC1") (pin "4") (pinfunction "RESET#_4") (pintype "bidirectional"))
      (node (ref "IC2") (pin "10") (pinfunction "OE_10") (pintype "input"))
      (node (ref "IC2") (pin "13") (pinfunction "OE_13") (pintype "input"))
      (node (ref "R25") (pin "1") (pinfunction "1_1") (pintype "passive"))
      (node (ref "R26") (pin "2") (pinfunction "2_2") (pintype "passive"))
    )
    (net (code "100") (name "USB_VDD") (class "Default")
      (node (ref "J1") (pin "27") (pinfunction "P$27_27") (pintype "passive"))
      (node (ref "R25") (pin "2") (pinfunction "2_2") (pintype "passive"))
    )
    (net (code "101") (name "unconnected-(CON1-P$6-Pad6)") (class "Default")
      (node (ref "CON1") (pin "6") (pinfunction "P$6_6") (pintype "bidirectional"))
    )
    (net (code "102") (name "unconnected-(CON1-P$7-Pad7)") (class "Default")
      (node (ref "CON1") (pin "7") (pinfunction "P$7_7") (pintype "bidirectional"))
    )
    (net (code "103") (name "unconnected-(D2-A-Pad3)") (class "Default")
      (node (ref "D2") (pin "3") (pinfunction "A_3") (pintype "passive"))
    )
    (net (code "104") (name "unconnected-(D3-A-Pad3)") (class "Default")
      (node (ref "D3") (pin "3") (pinfunction "A_3") (pintype "passive"))
    )
    (net (code "105") (name "unconnected-(DISPLAY-ADR0(CLK)-PadP$9)") (class "Default")
      (node (ref "DISPLAY") (pin "P$9") (pinfunction "ADR0(CLK)_P$9") (pintype "bidirectional"))
    )
    (net (code "106") (name "unconnected-(DISPLAY-ADR1(CPOL)-PadP$14)") (class "Default")
      (node (ref "DISPLAY") (pin "P$14") (pinfunction "ADR1(CPOL)_P$14") (pintype "bidirectional"))
    )
    (net (code "107") (name "unconnected-(DISPLAY-ADR2(CPHA)-PadP$15)") (class "Default")
      (node (ref "DISPLAY") (pin "P$15") (pinfunction "ADR2(CPHA)_P$15") (pintype "bidirectional"))
    )
    (net (code "108") (name "unconnected-(DISPLAY-BUZZ-PadP$16)") (class "Default")
      (node (ref "DISPLAY") (pin "P$16") (pinfunction "BUZZ_P$16") (pintype "bidirectional"))
    )
    (net (code "109") (name "unconnected-(DISPLAY-DPOM-PadP$13)") (class "Default")
      (node (ref "DISPLAY") (pin "P$13") (pinfunction "DPOM_P$13") (pintype "bidirectional"))
    )
    (net (code "110") (name "unconnected-(DISPLAY-DPROT-PadP$17)") (class "Default")
      (node (ref "DISPLAY") (pin "P$17") (pinfunction "DPROT_P$17") (pintype "bidirectional"))
    )
    (net (code "111") (name "unconnected-(DISPLAY-EN485-PadP$12)") (class "Default")
      (node (ref "DISPLAY") (pin "P$12") (pinfunction "EN485_P$12") (pintype "bidirectional"))
    )
    (net (code "112") (name "unconnected-(DISPLAY-TEST_SBUF-PadP$20)") (class "Default")
      (node (ref "DISPLAY") (pin "P$20") (pinfunction "TEST_SBUF_P$20") (pintype "bidirectional"))
    )
    (net (code "113") (name "unconnected-(DISPLAY-WP-PadP$19)") (class "Default")
      (node (ref "DISPLAY") (pin "P$19") (pinfunction "WP_P$19") (pintype "bidirectional"))
    )
    (net (code "114") (name "unconnected-(IC1-ACBUS0-Pad15)") (class "Default")
      (node (ref "IC1") (pin "15") (pinfunction "ACBUS0_15") (pintype "bidirectional"))
    )
    (net (code "115") (name "unconnected-(IC1-ACBUS1-Pad13)") (class "Default")
      (node (ref "IC1") (pin "13") (pinfunction "ACBUS1_13") (pintype "bidirectional"))
    )
    (net (code "116") (name "unconnected-(IC1-ACBUS2-Pad12)") (class "Default")
      (node (ref "IC1") (pin "12") (pinfunction "ACBUS2_12") (pintype "bidirectional"))
    )
    (net (code "117") (name "unconnected-(IC1-ACBUS3-Pad11)") (class "Default")
      (node (ref "IC1") (pin "11") (pinfunction "ACBUS3_11") (pintype "bidirectional"))
    )
    (net (code "118") (name "unconnected-(IC1-ADBUS2-Pad22)") (class "Default")
      (node (ref "IC1") (pin "22") (pinfunction "ADBUS2_22") (pintype "bidirectional"))
    )
    (net (code "119") (name "unconnected-(IC1-ADBUS3-Pad21)") (class "Default")
      (node (ref "IC1") (pin "21") (pinfunction "ADBUS3_21") (pintype "bidirectional"))
    )
    (net (code "120") (name "unconnected-(IC1-ADBUS4-Pad20)") (class "Default")
      (node (ref "IC1") (pin "20") (pinfunction "ADBUS4_20") (pintype "bidirectional"))
    )
    (net (code "121") (name "unconnected-(IC1-ADBUS5-Pad19)") (class "Default")
      (node (ref "IC1") (pin "19") (pinfunction "ADBUS5_19") (pintype "bidirectional"))
    )
    (net (code "122") (name "unconnected-(IC1-ADBUS6-Pad17)") (class "Default")
      (node (ref "IC1") (pin "17") (pinfunction "ADBUS6_17") (pintype "bidirectional"))
    )
    (net (code "123") (name "unconnected-(IC1-ADBUS7-Pad16)") (class "Default")
      (node (ref "IC1") (pin "16") (pinfunction "ADBUS7_16") (pintype "bidirectional"))
    )
    (net (code "124") (name "unconnected-(IC1-BCBUS0-Pad30)") (class "Default")
      (node (ref "IC1") (pin "30") (pinfunction "BCBUS0_30") (pintype "bidirectional"))
    )
    (net (code "125") (name "unconnected-(IC1-BCBUS1-Pad29)") (class "Default")
      (node (ref "IC1") (pin "29") (pinfunction "BCBUS1_29") (pintype "bidirectional"))
    )
    (net (code "126") (name "unconnected-(IC1-BCBUS2-Pad28)") (class "Default")
      (node (ref "IC1") (pin "28") (pinfunction "BCBUS2_28") (pintype "bidirectional"))
    )
    (net (code "127") (name "unconnected-(IC1-BCBUS3-Pad27)") (class "Default")
      (node (ref "IC1") (pin "27") (pinfunction "BCBUS3_27") (pintype "bidirectional"))
    )
    (net (code "128") (name "unconnected-(IC1-BDBUS0-Pad40)") (class "Default")
      (node (ref "IC1") (pin "40") (pinfunction "BDBUS0_40") (pintype "bidirectional"))
    )
    (net (code "129") (name "unconnected-(IC1-BDBUS1-Pad39)") (class "Default")
      (node (ref "IC1") (pin "39") (pinfunction "BDBUS1_39") (pintype "bidirectional"))
    )
    (net (code "130") (name "unconnected-(IC1-BDBUS2-Pad38)") (class "Default")
      (node (ref "IC1") (pin "38") (pinfunction "BDBUS2_38") (pintype "bidirectional"))
    )
    (net (code "131") (name "unconnected-(IC1-BDBUS3-Pad37)") (class "Default")
      (node (ref "IC1") (pin "37") (pinfunction "BDBUS3_37") (pintype "bidirectional"))
    )
    (net (code "132") (name "unconnected-(IC1-BDBUS4-Pad36)") (class "Default")
      (node (ref "IC1") (pin "36") (pinfunction "BDBUS4_36") (pintype "bidirectional"))
    )
    (net (code "133") (name "unconnected-(IC1-BDBUS5-Pad35)") (class "Default")
      (node (ref "IC1") (pin "35") (pinfunction "BDBUS5_35") (pintype "bidirectional"))
    )
    (net (code "134") (name "unconnected-(IC1-BDBUS6-Pad33)") (class "Default")
      (node (ref "IC1") (pin "33") (pinfunction "BDBUS6_33") (pintype "bidirectional"))
    )
    (net (code "135") (name "unconnected-(IC1-BDBUS7-Pad32)") (class "Default")
      (node (ref "IC1") (pin "32") (pinfunction "BDBUS7_32") (pintype "bidirectional"))
    )
    (net (code "136") (name "unconnected-(IC1-EECS-Pad48)") (class "Default")
      (node (ref "IC1") (pin "48") (pinfunction "EECS_48") (pintype "bidirectional"))
    )
    (net (code "137") (name "unconnected-(IC1-EESK-Pad1)") (class "Default")
      (node (ref "IC1") (pin "1") (pinfunction "EESK_1") (pintype "bidirectional"))
    )
    (net (code "138") (name "unconnected-(IC1-PWREN#-Pad41)") (class "Default")
      (node (ref "IC1") (pin "41") (pinfunction "PWREN#_41") (pintype "bidirectional"))
    )
    (net (code "139") (name "unconnected-(IC1-SI{slash}WUA-Pad10)") (class "Default")
      (node (ref "IC1") (pin "10") (pinfunction "SI/WUA_10") (pintype "bidirectional"))
    )
    (net (code "140") (name "unconnected-(IC1-SI{slash}WUB-Pad26)") (class "Default")
      (node (ref "IC1") (pin "26") (pinfunction "SI/WUB_26") (pintype "bidirectional"))
    )
    (net (code "141") (name "unconnected-(IC2A-O-Pad3)") (class "Default")
      (node (ref "IC2") (pin "3") (pinfunction "O_3") (pintype "tri_state"))
    )
    (net (code "142") (name "unconnected-(IC2B-O-Pad6)") (class "Default")
      (node (ref "IC2") (pin "6") (pinfunction "O_6") (pintype "tri_state"))
    )
    (net (code "143") (name "unconnected-(IC3-OUT1-Pad19)") (class "Default")
      (node (ref "IC3") (pin "19") (pinfunction "OUT1_19") (pintype "output"))
    )
    (net (code "144") (name "unconnected-(IC3-OUT2-Pad18)") (class "Default")
      (node (ref "IC3") (pin "18") (pinfunction "OUT2_18") (pintype "output"))
    )
    (net (code "145") (name "unconnected-(IC3-OUT3-Pad17)") (class "Default")
      (node (ref "IC3") (pin "17") (pinfunction "OUT3_17") (pintype "output"))
    )
    (net (code "146") (name "unconnected-(IC4-OUT1-Pad19)") (class "Default")
      (node (ref "IC4") (pin "19") (pinfunction "OUT1_19") (pintype "output"))
    )
    (net (code "147") (name "unconnected-(IC4-OUT7-Pad13)") (class "Default")
      (node (ref "IC4") (pin "13") (pinfunction "OUT7_13") (pintype "output"))
    )
    (net (code "148") (name "unconnected-(IC4-OUT8-Pad12)") (class "Default")
      (node (ref "IC4") (pin "12") (pinfunction "OUT8_12") (pintype "output"))
    )
    (net (code "149") (name "unconnected-(IC5-DIG3-Pad7)") (class "Default")
      (node (ref "IC5") (pin "7") (pinfunction "DIG3_7") (pintype "output"))
    )
    (net (code "150") (name "unconnected-(IC5-DIG4-Pad3)") (class "Default")
      (node (ref "IC5") (pin "3") (pinfunction "DIG4_3") (pintype "output"))
    )
    (net (code "151") (name "unconnected-(IC5-DIG5-Pad10)") (class "Default")
      (node (ref "IC5") (pin "10") (pinfunction "DIG5_10") (pintype "output"))
    )
    (net (code "152") (name "unconnected-(IC5-DIG6-Pad5)") (class "Default")
      (node (ref "IC5") (pin "5") (pinfunction "DIG6_5") (pintype "output"))
    )
    (net (code "153") (name "unconnected-(IC5-DIG7-Pad8)") (class "Default")
      (node (ref "IC5") (pin "8") (pinfunction "DIG7_8") (pintype "output"))
    )
    (net (code "154") (name "unconnected-(IC5-DOUT-Pad24)") (class "Default")
      (node (ref "IC5") (pin "24") (pinfunction "DOUT_24") (pintype "output"))
    )
    (net (code "155") (name "unconnected-(IC5-SEGDP-Pad22)") (class "Default")
      (node (ref "IC5") (pin "22") (pinfunction "SEGDP_22") (pintype "output"))
    )
    (net (code "156") (name "unconnected-(IC5-SEGF-Pad15)") (class "Default")
      (node (ref "IC5") (pin "15") (pinfunction "SEGF_15") (pintype "output"))
    )
    (net (code "157") (name "unconnected-(IC5-SEGG-Pad17)") (class "Default")
      (node (ref "IC5") (pin "17") (pinfunction "SEGG_17") (pintype "output"))
    )
    (net (code "158") (name "unconnected-(U1A-P5.2-Pad15)") (class "Default")
      (node (ref "U1") (pin "15") (pinfunction "P5.2_15") (pintype "bidirectional"))
    )
    (net (code "159") (name "unconnected-(U1A-P5.15-Pad23)") (class "Default")
      (node (ref "U1") (pin "23") (pinfunction "P5.15_23") (pintype "bidirectional"))
    )
    (net (code "160") (name "unconnected-(U1A-P6.0-Pad7)") (class "Default")
      (node (ref "U1") (pin "7") (pinfunction "P6.0_7") (pintype "bidirectional"))
    )
    (net (code "161") (name "unconnected-(U1A-P6.1-Pad8)") (class "Default")
      (node (ref "U1") (pin "8") (pinfunction "P6.1_8") (pintype "bidirectional"))
    )
    (net (code "162") (name "unconnected-(U1A-P10.7-Pad47)") (class "Default")
      (node (ref "U1") (pin "47") (pinfunction "P10.7_47") (pintype "bidirectional"))
    )
    (net (code "163") (name "unconnected-(U1A-P10.8-Pad51)") (class "Default")
      (node (ref "U1") (pin "51") (pinfunction "P10.8_51") (pintype "bidirectional"))
    )
    (net (code "164") (name "unconnected-(U1A-P10.14-Pad58)") (class "Default")
      (node (ref "U1") (pin "58") (pinfunction "P10.14_58") (pintype "bidirectional"))
    )
    (net (code "165") (name "unconnected-(U1A-P15.0-Pad10)") (class "Default")
      (node (ref "U1") (pin "10") (pinfunction "P15.0_10") (pintype "input"))
    )
    (net (code "166") (name "unconnected-(U1A-P15.4-Pad11)") (class "Default")
      (node (ref "U1") (pin "11") (pinfunction "P15.4_11") (pintype "input"))
    )
    (net (code "167") (name "~{PORST}") (class "Default")
      (node (ref "C20") (pin "2") (pinfunction "2_2") (pintype "passive"))
      (node (ref "CON1") (pin "10") (pinfunction "P$10_10") (pintype "bidirectional"))
      (node (ref "J1") (pin "15") (pinfunction "P$15_15") (pintype "passive"))
      (node (ref "R19") (pin "1") (pinfunction "1_1") (pintype "passive"))
      (node (ref "U1") (pin "62") (pinfunction "~{PORST}_62") (pintype "input"))
    )
    (net (code "168") (name "~{TRST}") (class "Default")
      (node (ref "CON1") (pin "8") (pinfunction "P$8_8") (pintype "bidirectional"))
      (node (ref "J1") (pin "17") (pinfunction "P$17_17") (pintype "passive"))
      (node (ref "R23") (pin "1") (pinfunction "1_1") (pintype "passive"))
      (node (ref "U1") (pin "4") (pinfunction "~{TRST}_4") (pintype "input"))
    )
    (net (code "169") (name "~{U0C1_SEL0}") (class "Default")
      (node (ref "IC5") (pin "12") (pinfunction "/CS_12") (pintype "input"))
      (node (ref "R5") (pin "1") (pinfunction "1_1") (pintype "passive"))
      (node (ref "U1") (pin "35") (pinfunction "P2.7_35") (pintype "bidirectional"))
    )
  )
)
